# BTL__SCHESchDoc.net
KiCad netlist of a schematic drawn in Altium Designer
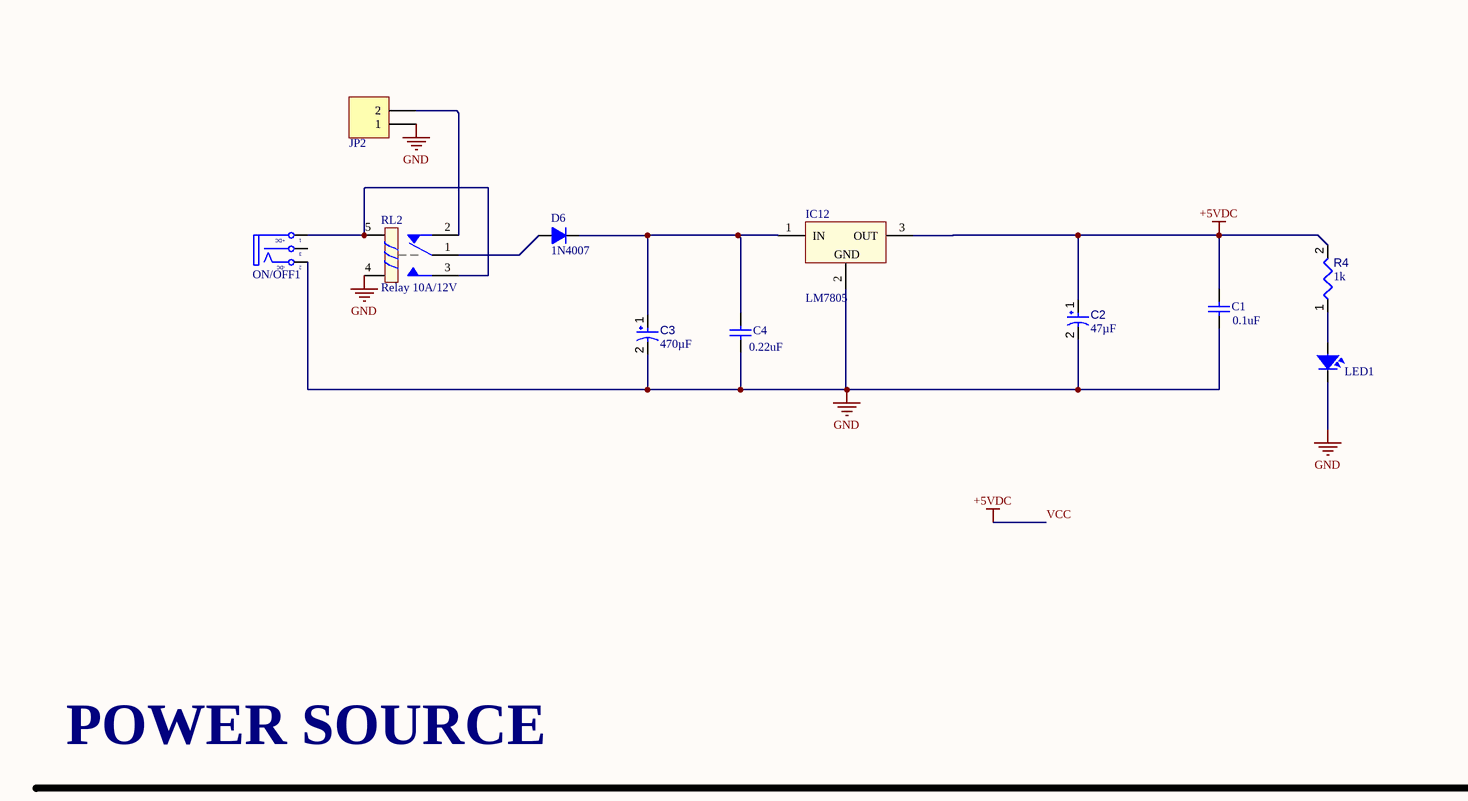
[diagram p0: BTL._SCHESchDoc.SchDoc, top left]
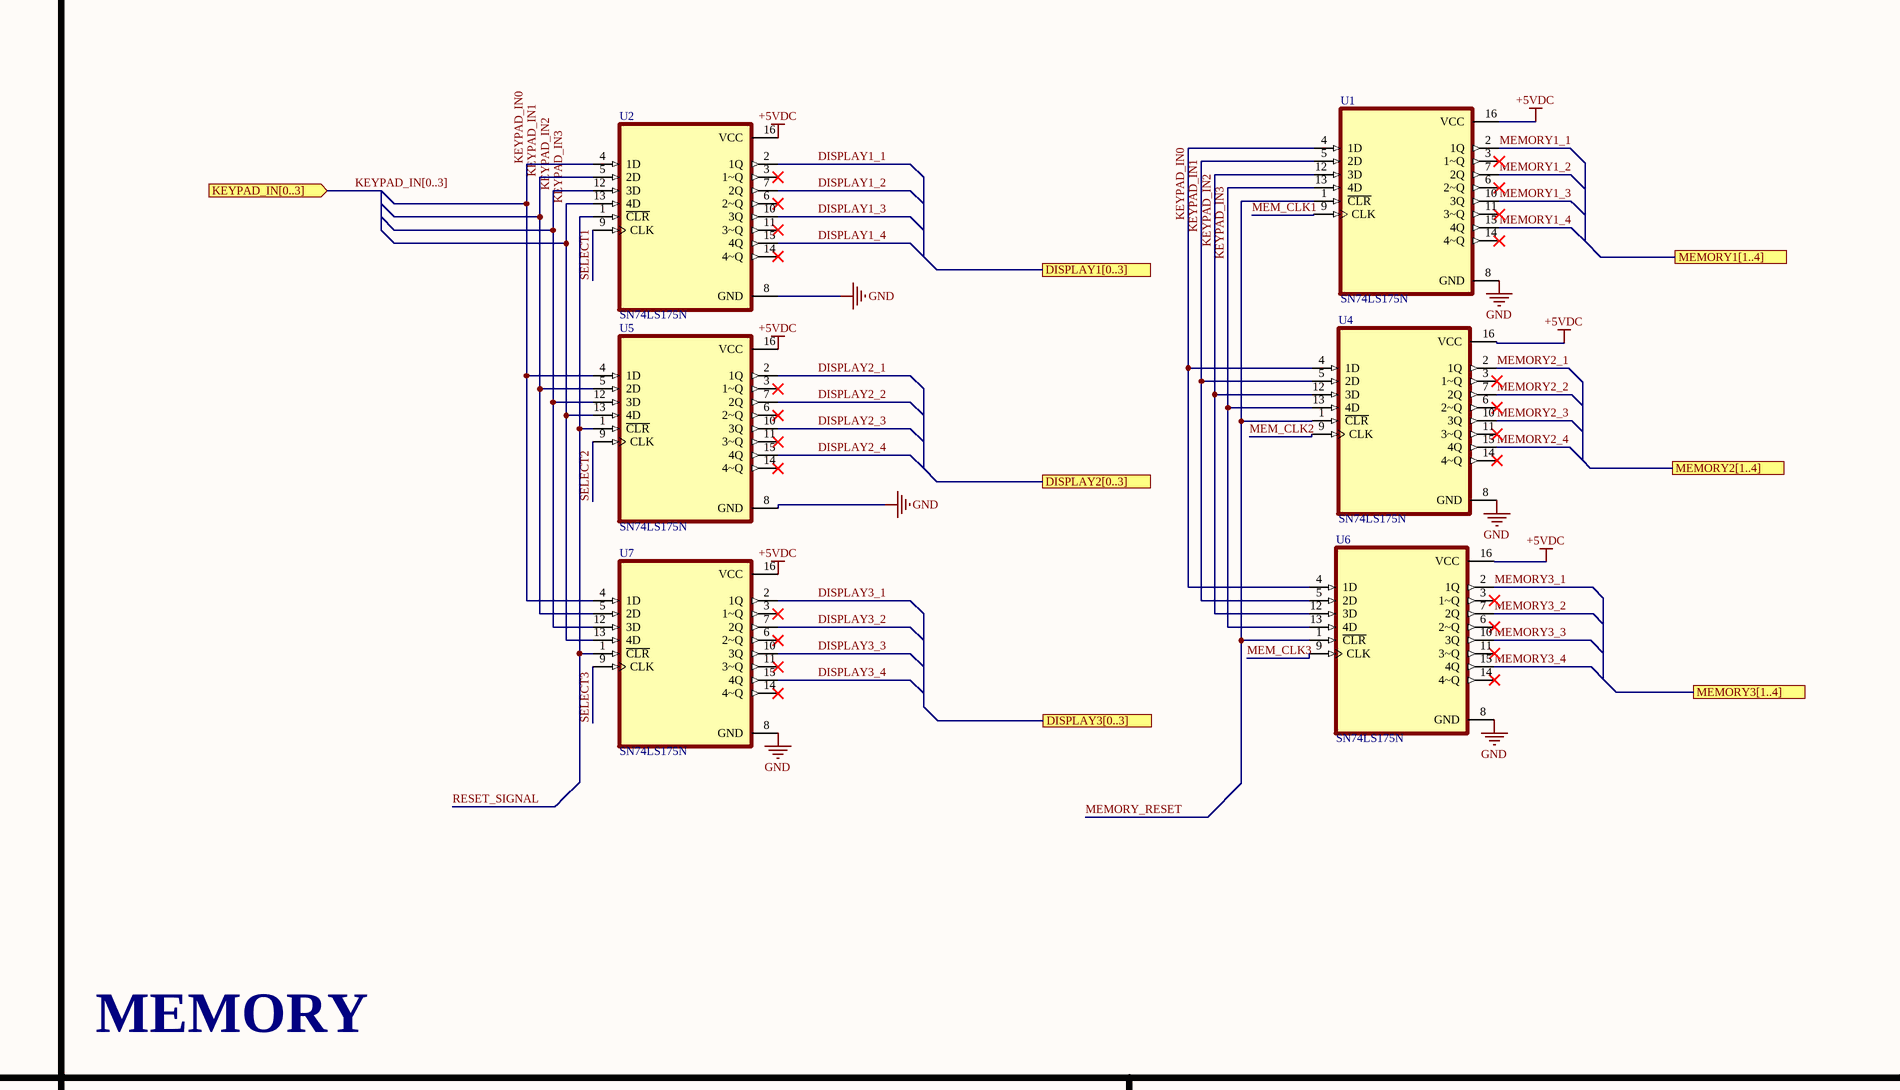
[diagram p1: BTL._SCHESchDoc.SchDoc, top middle]
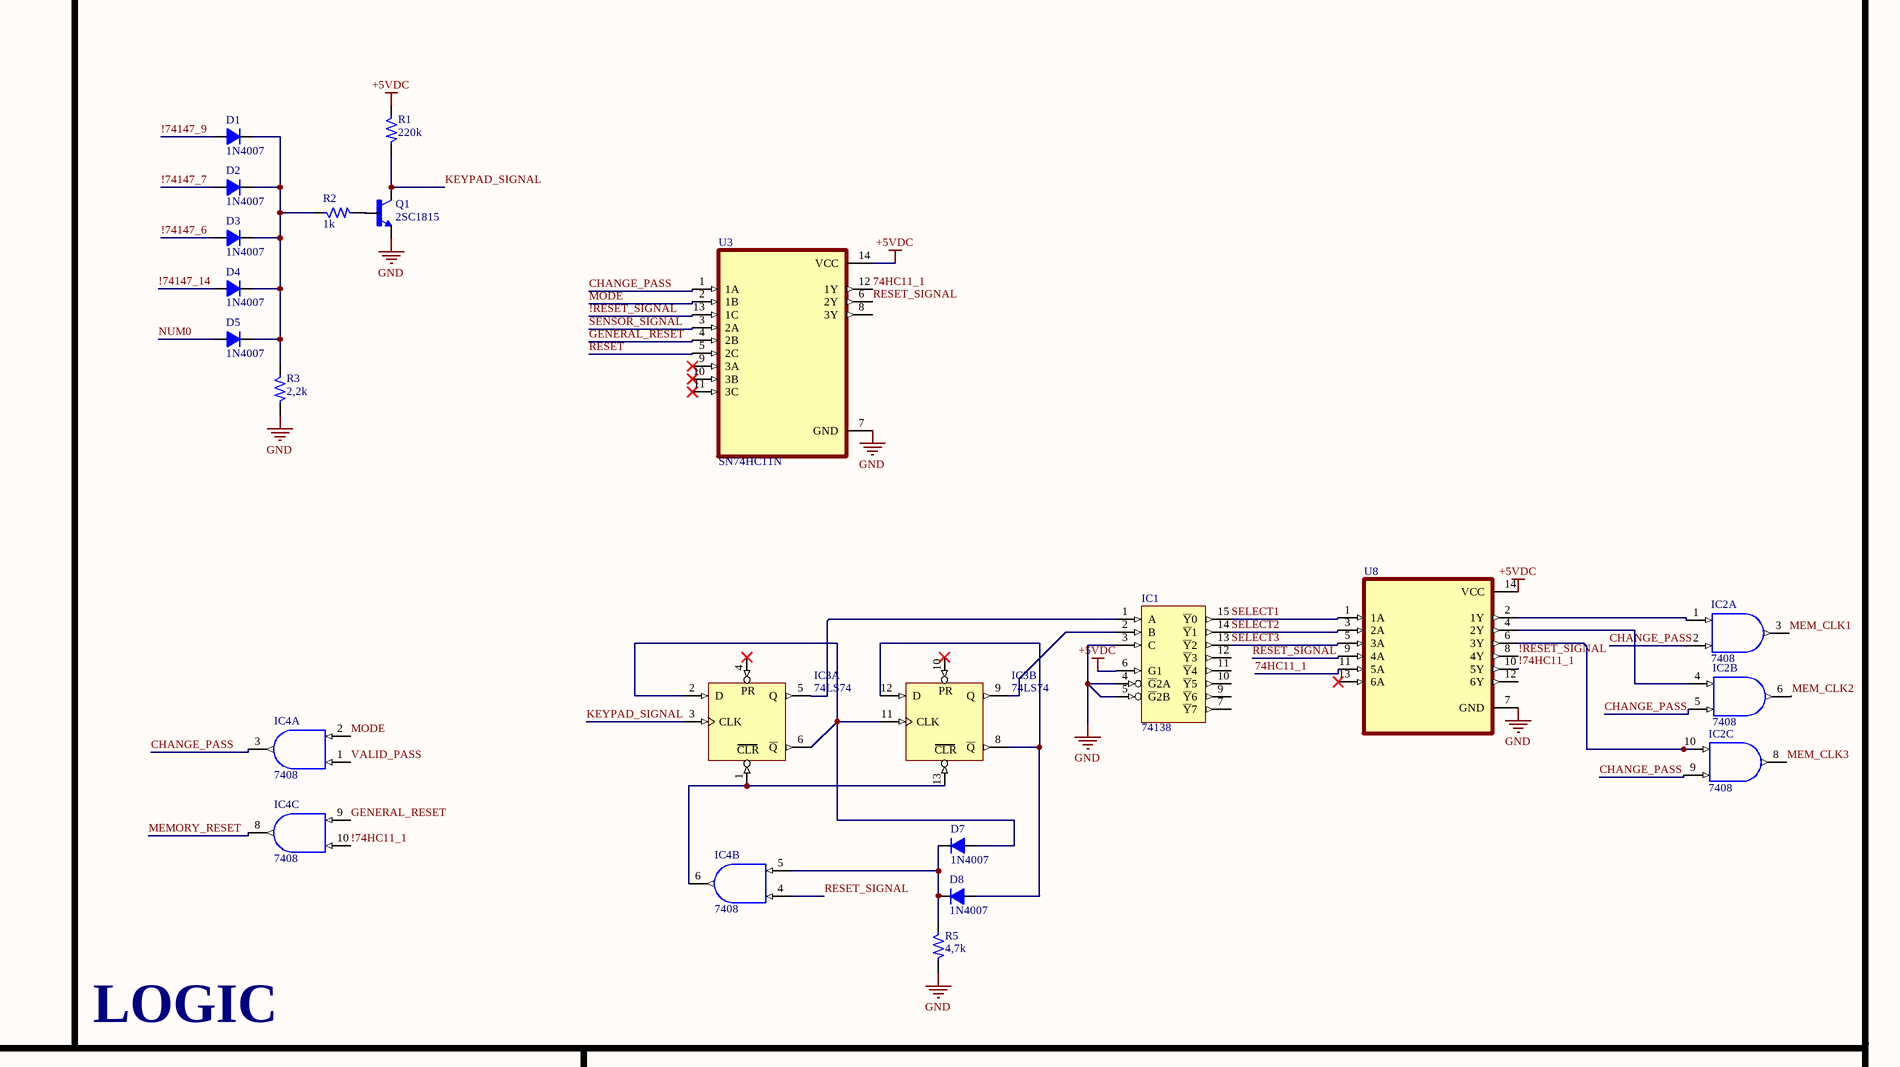
[diagram p2: BTL._SCHESchDoc.SchDoc, top right]
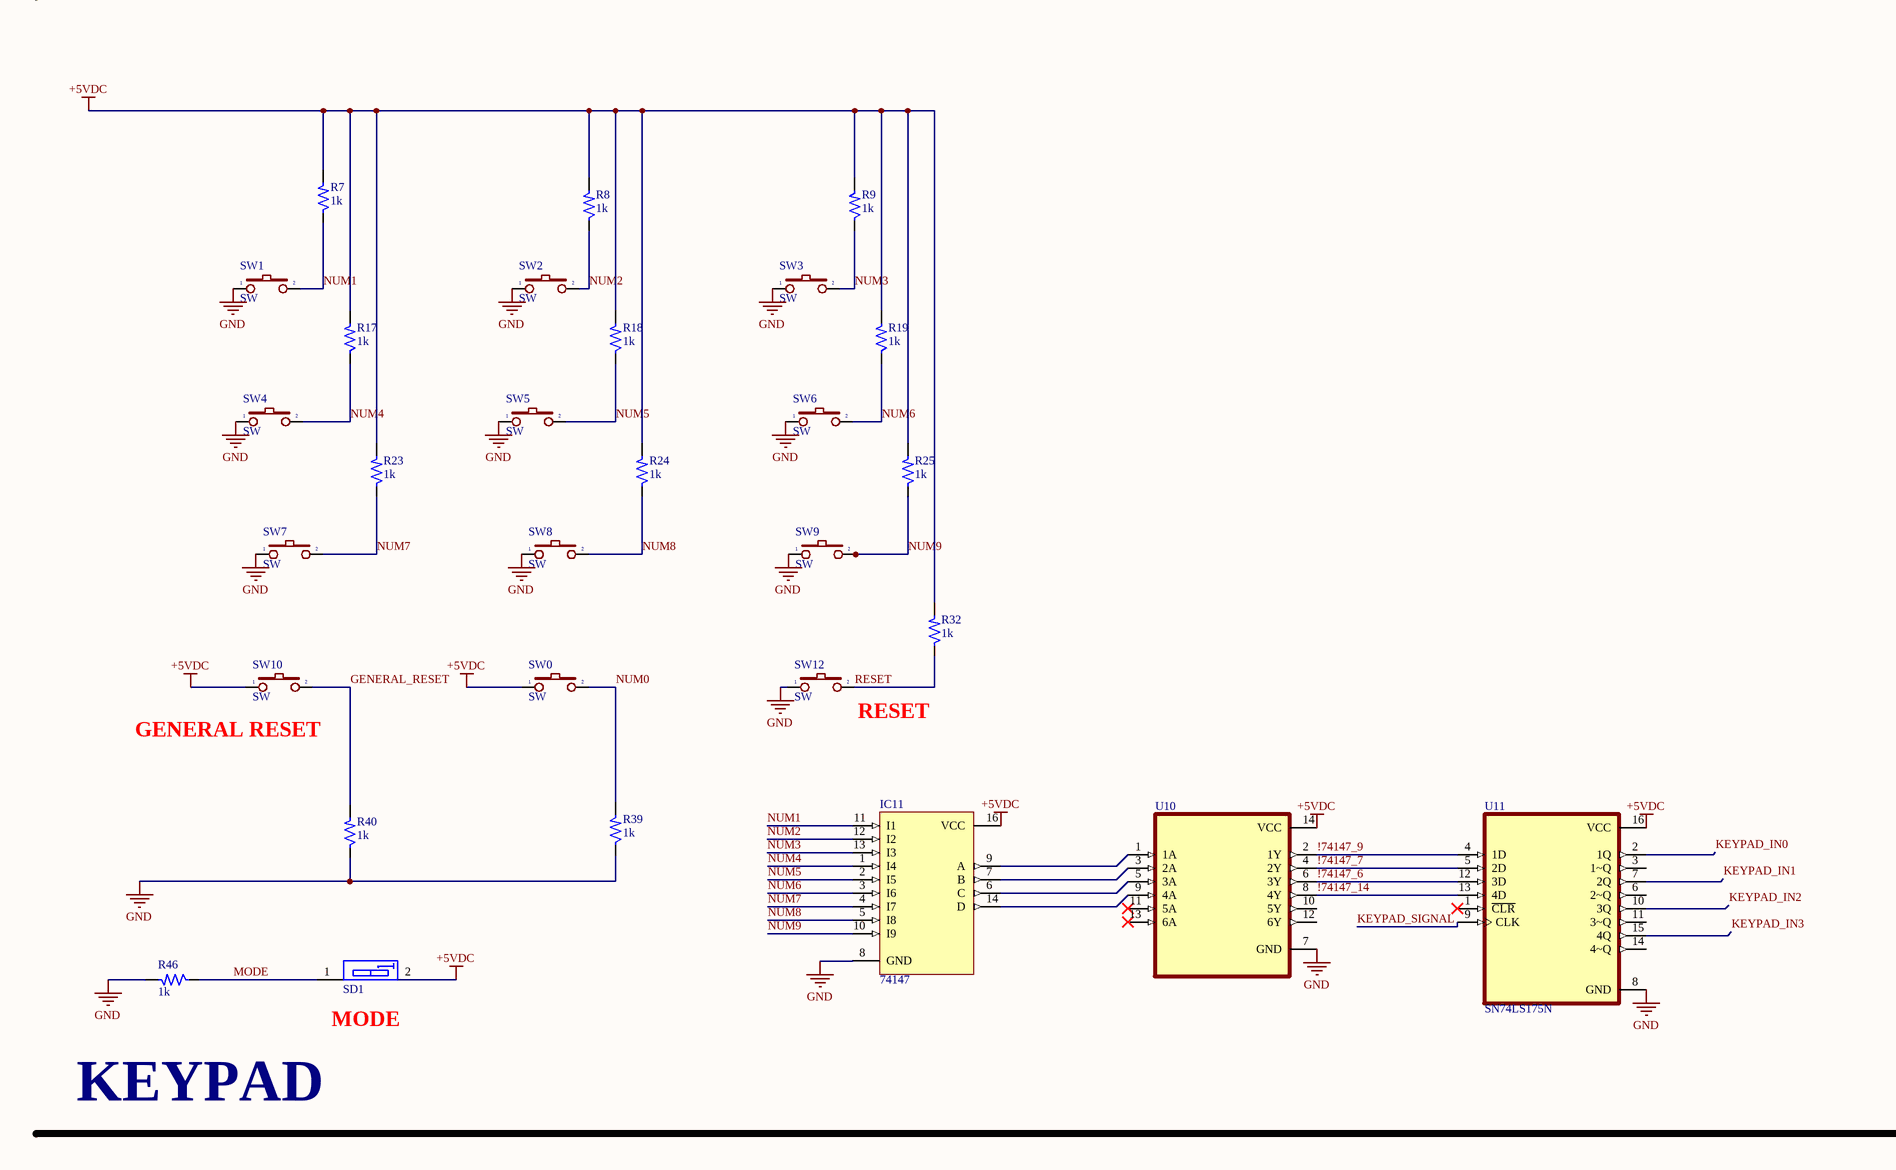
[diagram p3: BTL._SCHESchDoc.SchDoc, bottom left]
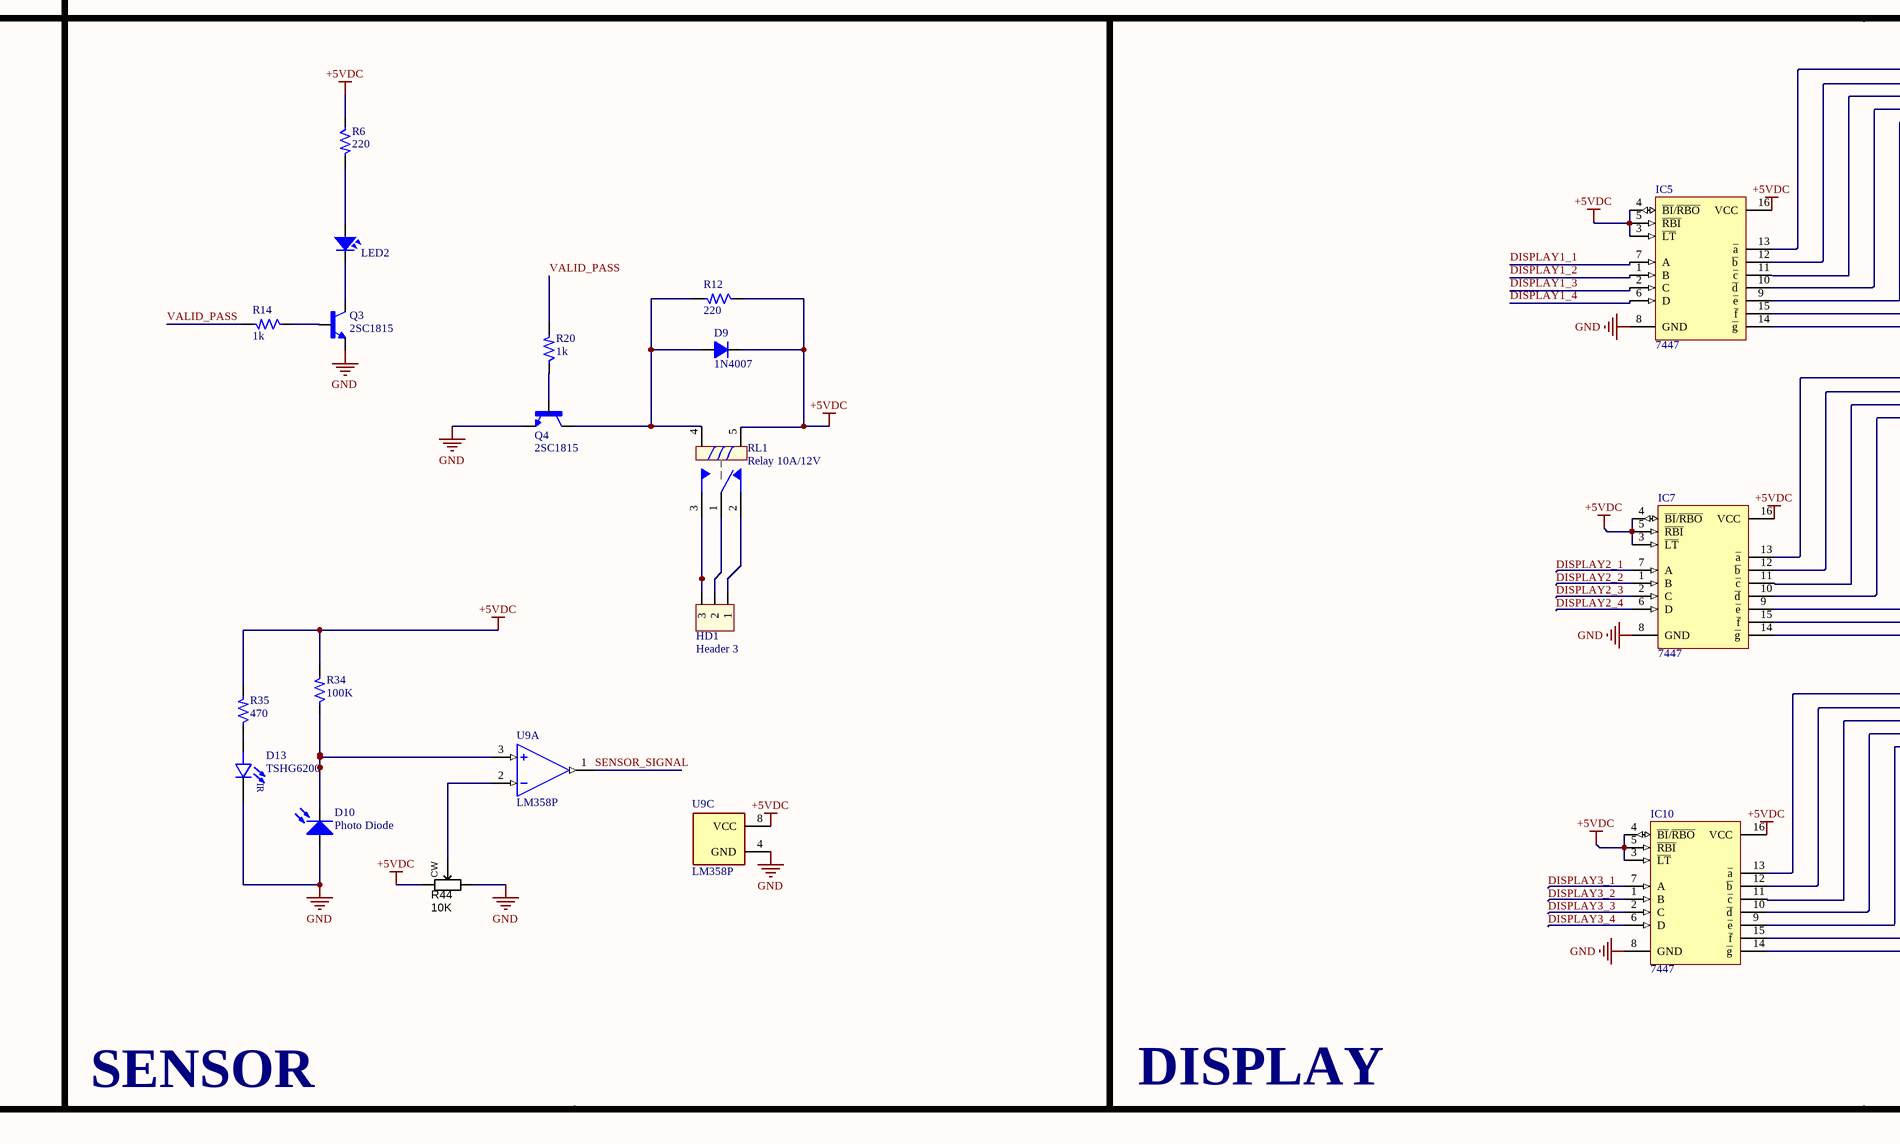
[diagram p4: BTL._SCHESchDoc.SchDoc, bottom middle]
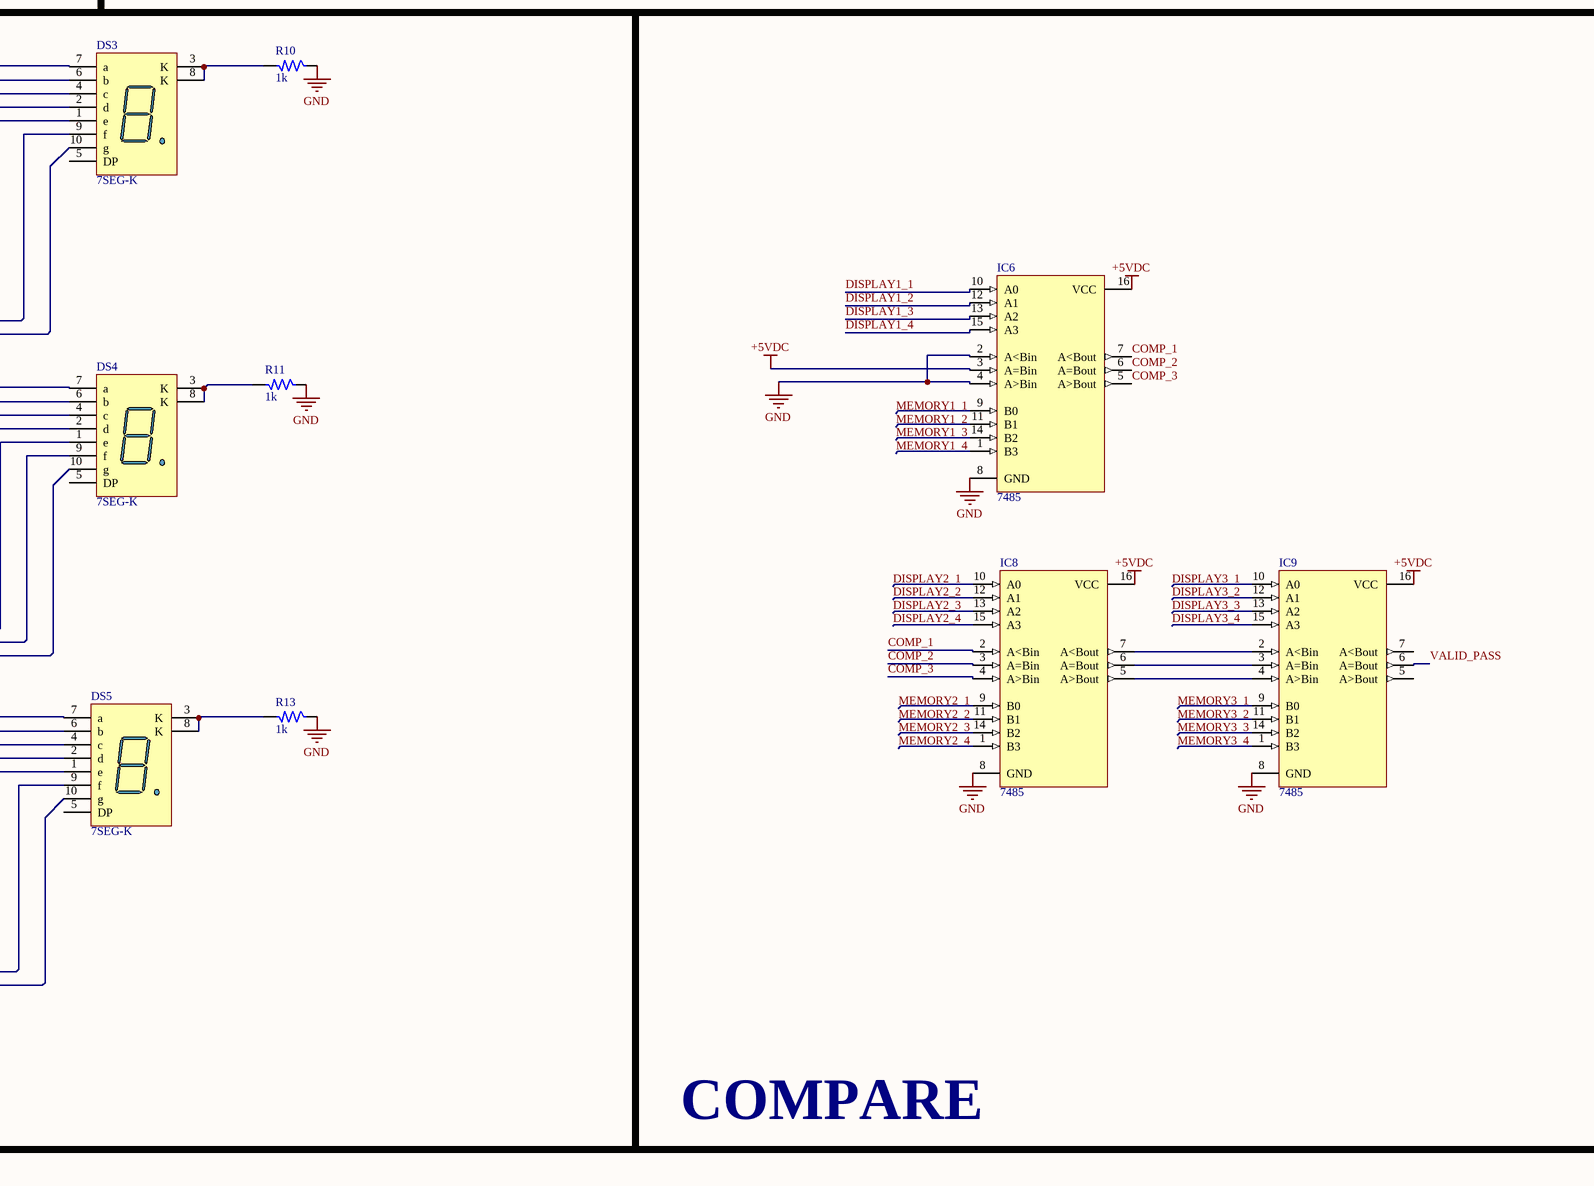
[diagram p5: BTL._SCHESchDoc.SchDoc, bottom right]

(export (version "E")
  (design (tool "Eeschema 10.0.6"))
  (components
    (comp (ref "C1")
      (value "Capacitor Ceramic 2KV")
      (footprint "103/2KV")
      (fields (field (name "PUBLISHER") "Altium Limited"))
      (libsource (lib "My library altium") (part "Cap 2KV"))
    )
    (comp (ref "C2")
      (value "47µF")
      (footprint "CAPPR55-250-1120X630X1220")
      (description "Aluminum Electrolytic Capacitor, 47 uF, +/-20%, 50 V, -40 to 85 degC, 2-Pin THD, RoHS, Bulk")
      (fields (field (name "TOLERANCE") "20%") (field (name "MANUFACTURER") "Panasonic"))
      (libsource (lib "Nam Nguyentbcm2711") (part "CAP-P-2"))
    )
    (comp (ref "C3")
      (value "470µF")
      (footprint "CAPPR65-500-2000X1000X2200")
      (description "Aluminum Electrolytic Capacitor, 470 uF, +/- 20%, 50 V, -40 to 85 degC, 2-Pin THD, RoHS, Bulk")
      (fields (field (name "TOLERANCE") "20%") (field (name "MANUFACTURER") "Panasonic"))
      (libsource (lib "Nam Nguyentbcm2711") (part "CAP-P-2"))
    )
    (comp (ref "C4")
      (value "Capacitor Ceramic 2KV")
      (footprint "103/2KV")
      (fields (field (name "PUBLISHER") "Altium Limited"))
      (libsource (lib "My library altium") (part "Cap 2KV"))
    )
    (comp (ref "D1")
      (value "1N4007")
      (footprint "D1A")
      (description "Diode 1A")
      (libsource (lib "syhaunguyen") (part "D1A"))
    )
    (comp (ref "D2")
      (value "1N4007")
      (footprint "D1A")
      (description "Diode 1A")
      (libsource (lib "syhaunguyen") (part "D1A"))
    )
    (comp (ref "D3")
      (value "1N4007")
      (footprint "D1A")
      (description "Diode 1A")
      (libsource (lib "syhaunguyen") (part "D1A"))
    )
    (comp (ref "D4")
      (value "1N4007")
      (footprint "D1A")
      (description "Diode 1A")
      (libsource (lib "syhaunguyen") (part "D1A"))
    )
    (comp (ref "D5")
      (value "1N4007")
      (footprint "D1A")
      (description "Diode 1A")
      (libsource (lib "syhaunguyen") (part "D1A"))
    )
    (comp (ref "D6")
      (value "1N4007")
      (footprint "D1A")
      (description "Diode 1A")
      (libsource (lib "syhaunguyen") (part "D1A"))
    )
    (comp (ref "D7")
      (value "1N4007")
      (footprint "D1A")
      (description "Diode 1A")
      (libsource (lib "syhaunguyen") (part "D1A"))
    )
    (comp (ref "D8")
      (value "1N4007")
      (footprint "D1A")
      (description "Diode 1A")
      (libsource (lib "syhaunguyen") (part "D1A"))
    )
    (comp (ref "D9")
      (value "1N4007")
      (footprint "D1A")
      (description "Diode 1A")
      (libsource (lib "syhaunguyen") (part "D1A"))
    )
    (comp (ref "D10")
      (value "Photo Diode")
      (footprint "LED-5")
      (description "Photosensitive Diode")
      (libsource (lib "My library altium") (part "Photo Diode"))
    )
    (comp (ref "D13")
      (value "TSHG6200")
      (footprint "LEDRD254W55D595H900")
      (description "850 nm 100 mA Â±10Â° Through Hole High Speed Infrared Emitting Diode - T-1 3/4 CT")
      (fields (field (name "MF") "{'manufacturer': u'Vishay'}"))
      (libsource (lib "SnapEDA_Library") (part "TSHG6200"))
    )
    (comp (ref "DS3")
      (value "7SEG-K")
      (footprint "LED7SEG")
      (description "14.2 mm General Purpose Blue 7-Segment Display: CC, RH DP, Gray Surface")
      (fields (field (name "PUBLISHER") "Altium Limited"))
      (libsource (lib "My library altium") (part "LED 7SEG-K"))
    )
    (comp (ref "DS4")
      (value "7SEG-K")
      (footprint "LED7SEG")
      (description "14.2 mm General Purpose Blue 7-Segment Display: CC, RH DP, Gray Surface")
      (fields (field (name "PUBLISHER") "Altium Limited"))
      (libsource (lib "My library altium") (part "LED 7SEG-K"))
    )
    (comp (ref "DS5")
      (value "7SEG-K")
      (footprint "LED7SEG")
      (description "14.2 mm General Purpose Blue 7-Segment Display: CC, RH DP, Gray Surface")
      (fields (field (name "PUBLISHER") "Altium Limited"))
      (libsource (lib "My library altium") (part "LED 7SEG-K"))
    )
    (comp (ref "HD1")
      (value "Header 3")
      (footprint "HED3")
      (description "Header 3 (Green)")
      (libsource (lib "syhaunguyen") (part "Hed3"))
    )
    (comp (ref "IC1")
      (value "74138")
      (footprint "DIP16/W0.3")
      (description "3 -to- 8 Decoder - Out Low")
      (fields (field (name "COPYRIGHT BY") "VanDungEvn@Gmail.com"))
      (libsource (lib "syhaunguyen") (part "74138"))
    )
    (comp (ref "IC2")
      (value "7408")
      (footprint "DIP14/W0.3")
      (description "Quad 2-Input AND Gate")
      (libsource (lib "My library altium") (part "7408"))
    )
    (comp (ref "IC3")
      (value "74LS74")
      (footprint "DIP14/W0.3")
      (description "Dual D Flip-Flop")
      (fields (field (name "COPYRIGHT BY") "VanDungEvn@Gmail.com"))
      (libsource (lib "syhaunguyen") (part "7474"))
    )
    (comp (ref "IC4")
      (value "7408")
      (footprint "DIP14/W0.3")
      (description "Quad 2-Input AND Gate")
      (libsource (lib "syhaunguyen") (part "7408"))
    )
    (comp (ref "IC5")
      (value "7447")
      (footprint "DIP16/W0.3")
      (description "BCD to 7-Segment Decoder/Driver")
      (libsource (lib "My library altium") (part "7447"))
    )
    (comp (ref "IC6")
      (value "7485")
      (footprint "DIP16/W0.3")
      (description "4-Bit Magnitude Comparator")
      (fields (field (name "COPYRIGHT BY") "VanDungEvn@Gmail.com"))
      (libsource (lib "My library altium") (part "7485"))
    )
    (comp (ref "IC7")
      (value "7447")
      (footprint "DIP16/W0.3")
      (description "BCD to 7-Segment Decoder/Driver")
      (libsource (lib "My library altium") (part "7447"))
    )
    (comp (ref "IC8")
      (value "7485")
      (footprint "DIP16/W0.3")
      (description "4-Bit Magnitude Comparator")
      (fields (field (name "COPYRIGHT BY") "VanDungEvn@Gmail.com"))
      (libsource (lib "My library altium") (part "7485"))
    )
    (comp (ref "IC9")
      (value "7485")
      (footprint "DIP16/W0.3")
      (description "4-Bit Magnitude Comparator")
      (fields (field (name "COPYRIGHT BY") "VanDungEvn@Gmail.com"))
      (libsource (lib "My library altium") (part "7485"))
    )
    (comp (ref "IC10")
      (value "7447")
      (footprint "DIP16/W0.3")
      (description "BCD to 7-Segment Decoder/Driver")
      (libsource (lib "My library altium") (part "7447"))
    )
    (comp (ref "IC11")
      (value "74147")
      (footprint "DIP16/W0.3")
      (description "10-Line to 4-Line Priority Encoder")
      (fields (field (name "COPYRIGHT BY") "VanDungEvn@Gmail.com"))
      (libsource (lib "My library altium") (part "74147"))
    )
    (comp (ref "IC12")
      (value "LM7805")
      (footprint "QTO-220")
      (description "On ap +, from + 5 to + 24VDC")
      (libsource (lib "My library altium") (part "LM78xx"))
    )
    (comp (ref "JP2")
      (value "Header 2_1")
      (footprint "HED2")
      (description "Header, 2-Pin")
      (fields (field (name "MANUFACTURER") "Generic Components"))
      (libsource (lib "syhaunguyen") (part "Header 2_1"))
    )
    (comp (ref "LED1")
      (value "LED")
      (footprint "LED-5-Green")
      (description "LED Single colour Green and Red")
      (libsource (lib "syhaunguyen") (part "LED"))
    )
    (comp (ref "LED2")
      (value "LED")
      (footprint "LED-5-Green")
      (description "LED Single colour Green and Red")
      (libsource (lib "syhaunguyen") (part "LED"))
    )
    (comp (ref "ON/OFF1")
      (value "POWER")
      (footprint "DC-IN")
      (libsource (lib "My library altium") (part "DCIN"))
    )
    (comp (ref "Q1")
      (value "2SC1815")
      (footprint "TO92127P521H534-3")
      (fields (field (name "MF") "{'manufacturer': u'Micro Commercial'}"))
      (libsource (lib "") (part "2SC1815_1"))
    )
    (comp (ref "Q3")
      (value "2SC1815")
      (footprint "TO92127P521H534-3")
      (fields (field (name "MF") "{'manufacturer': u'Micro Commercial'}"))
      (libsource (lib "") (part "2SC1815_1"))
    )
    (comp (ref "Q4")
      (value "2SC1815")
      (footprint "TO92127P521H534-3")
      (fields (field (name "MF") "{'manufacturer': u'Micro Commercial'}"))
      (libsource (lib "SnapEDA_Library") (part "2SC1815"))
    )
    (comp (ref "R1")
      (value "220k")
      (footprint "R1/4W3")
      (description "Res")
      (libsource (lib "My library altium") (part "Res"))
    )
    (comp (ref "R2")
      (value "1k")
      (footprint "R1/4W3")
      (description "Res")
      (libsource (lib "My library altium") (part "Res"))
    )
    (comp (ref "R3")
      (value "2,2k")
      (footprint "R1/4W3")
      (description "Res")
      (libsource (lib "My library altium") (part "Res"))
    )
    (comp (ref "R4")
      (value "1k")
      (footprint "RESA60-630X240")
      (description "Axial Resistor, 1 KOhm, +/- 1%, 250 mW, -55 to 155 degC, 2-Pin THD, RoHS, Bulk")
      (fields (field (name "TOLERANCE") "1%") (field (name "POWER") "250mW"))
      (libsource (lib "Nam Nguyentbcm2711") (part "RES-2"))
    )
    (comp (ref "R5")
      (value "4,7k")
      (footprint "R1/4W3")
      (description "Res")
      (libsource (lib "My library altium") (part "Res"))
    )
    (comp (ref "R6")
      (value "220")
      (footprint "R1/4W3")
      (description "Res")
      (libsource (lib "My library altium") (part "Res"))
    )
    (comp (ref "R7")
      (value "1k")
      (footprint "R1/4W3")
      (description "Res")
      (libsource (lib "My library altium") (part "Res"))
    )
    (comp (ref "R8")
      (value "1k")
      (footprint "R1/4W3")
      (description "Res")
      (libsource (lib "My library altium") (part "Res"))
    )
    (comp (ref "R9")
      (value "1k")
      (footprint "R1/4W3")
      (description "Res")
      (libsource (lib "My library altium") (part "Res"))
    )
    (comp (ref "R10")
      (value "1k")
      (footprint "R1/4W3")
      (description "Res")
      (libsource (lib "My library altium") (part "Res"))
    )
    (comp (ref "R11")
      (value "1k")
      (footprint "R1/4W3")
      (description "Res")
      (libsource (lib "My library altium") (part "Res"))
    )
    (comp (ref "R12")
      (value "220")
      (footprint "R1/4W3")
      (description "Res")
      (libsource (lib "My library altium") (part "Res"))
    )
    (comp (ref "R13")
      (value "1k")
      (footprint "R1/4W3")
      (description "Res")
      (libsource (lib "My library altium") (part "Res"))
    )
    (comp (ref "R14")
      (value "1k")
      (footprint "R1/4W3")
      (description "Res")
      (libsource (lib "My library altium") (part "Res"))
    )
    (comp (ref "R17")
      (value "1k")
      (footprint "R1/4W3")
      (description "Res")
      (libsource (lib "My library altium") (part "Res"))
    )
    (comp (ref "R18")
      (value "1k")
      (footprint "R1/4W3")
      (description "Res")
      (libsource (lib "My library altium") (part "Res"))
    )
    (comp (ref "R19")
      (value "1k")
      (footprint "R1/4W3")
      (description "Res")
      (libsource (lib "My library altium") (part "Res"))
    )
    (comp (ref "R20")
      (value "1k")
      (footprint "R1/4W3")
      (description "Res")
      (libsource (lib "My library altium") (part "Res"))
    )
    (comp (ref "R23")
      (value "1k")
      (footprint "R1/4W3")
      (description "Res")
      (libsource (lib "My library altium") (part "Res"))
    )
    (comp (ref "R24")
      (value "1k")
      (footprint "R1/4W3")
      (description "Res")
      (libsource (lib "My library altium") (part "Res"))
    )
    (comp (ref "R25")
      (value "1k")
      (footprint "R1/4W3")
      (description "Res")
      (libsource (lib "My library altium") (part "Res"))
    )
    (comp (ref "R32")
      (value "1k")
      (footprint "R1/4W3")
      (description "Res")
      (libsource (lib "My library altium") (part "Res"))
    )
    (comp (ref "R34")
      (value "100K")
      (footprint "R1/4W3")
      (description "Res")
      (libsource (lib "My library altium") (part "Res"))
    )
    (comp (ref "R35")
      (value "470")
      (footprint "R1/4W3")
      (description "Res")
      (libsource (lib "My library altium") (part "Res"))
    )
    (comp (ref "R39")
      (value "1k")
      (footprint "R1/4W3")
      (description "Res")
      (libsource (lib "My library altium") (part "Res"))
    )
    (comp (ref "R40")
      (value "1k")
      (footprint "R1/4W3")
      (description "Res")
      (libsource (lib "My library altium") (part "Res"))
    )
    (comp (ref "R44")
      (value "10K")
      (footprint "POT_3306F")
      (description "Trimmer THD 10K 200mW Single-turn")
      (fields (field (name "TOLERANCE") "±25%") (field (name "Comment") "Single-turn pot"))
      (libsource (lib "My library altium") (part "RES_TRIMMER_10K_1T_THT"))
    )
    (comp (ref "R46")
      (value "1k")
      (footprint "R1/4W3")
      (description "Res")
      (libsource (lib "My library altium") (part "Res"))
    )
    (comp (ref "RL1")
      (value "Relay 10A/12V")
      (footprint "RL_SPDT_10A")
      (description "Relay SPDT,10A - 12VDC 5 Pin")
      (libsource (lib "") (part "Relay 1_1"))
    )
    (comp (ref "RL2")
      (value "Relay 10A/12V")
      (footprint "RL_SPDT_10A")
      (description "Relay SPDT,10A - 12VDC 5 Pin")
      (libsource (lib "syhaunguyen") (part "Relay 1"))
    )
    (comp (ref "SD1")
      (value "SW - DIP2")
      (footprint "DIP2/W0.3K")
      (description "DIP Switch, 2 Position, SPST")
      (libsource (lib "My library altium") (part "SWDIP-1"))
    )
    (comp (ref "SW0")
      (value "SW")
      (footprint "SW2")
      (description "Switch button 2 pin")
      (libsource (lib "syhaunguyen") (part "SW2"))
    )
    (comp (ref "SW1")
      (value "SW")
      (footprint "SW2")
      (description "Switch button 2 pin")
      (libsource (lib "syhaunguyen") (part "SW2"))
    )
    (comp (ref "SW2")
      (value "SW")
      (footprint "SW2")
      (description "Switch button 2 pin")
      (libsource (lib "syhaunguyen") (part "SW2"))
    )
    (comp (ref "SW3")
      (value "SW")
      (footprint "SW2")
      (description "Switch button 2 pin")
      (libsource (lib "syhaunguyen") (part "SW2"))
    )
    (comp (ref "SW4")
      (value "SW")
      (footprint "SW2")
      (description "Switch button 2 pin")
      (libsource (lib "syhaunguyen") (part "SW2"))
    )
    (comp (ref "SW5")
      (value "SW")
      (footprint "SW2")
      (description "Switch button 2 pin")
      (libsource (lib "syhaunguyen") (part "SW2"))
    )
    (comp (ref "SW6")
      (value "SW")
      (footprint "SW2")
      (description "Switch button 2 pin")
      (libsource (lib "syhaunguyen") (part "SW2"))
    )
    (comp (ref "SW7")
      (value "SW")
      (footprint "SW2")
      (description "Switch button 2 pin")
      (libsource (lib "syhaunguyen") (part "SW2"))
    )
    (comp (ref "SW8")
      (value "SW")
      (footprint "SW2")
      (description "Switch button 2 pin")
      (libsource (lib "syhaunguyen") (part "SW2"))
    )
    (comp (ref "SW9")
      (value "SW")
      (footprint "SW2")
      (description "Switch button 2 pin")
      (libsource (lib "syhaunguyen") (part "SW2"))
    )
    (comp (ref "SW10")
      (value "SW")
      (footprint "SW2")
      (description "Switch button 2 pin")
      (libsource (lib "syhaunguyen") (part "SW2"))
    )
    (comp (ref "SW12")
      (value "SW")
      (footprint "SW2")
      (description "Switch button 2 pin")
      (libsource (lib "syhaunguyen") (part "SW2"))
    )
    (comp (ref "U1")
      (value "SN74LS175N")
      (footprint "DIP16")
      (fields (field (name "MF") "{'manufacturer': u'Texas Instruments'}"))
      (libsource (lib "SnapEDA_Library") (part "SN74LS175N"))
    )
    (comp (ref "U2")
      (value "SN74LS175N")
      (footprint "DIP16")
      (fields (field (name "MF") "{'manufacturer': u'Texas Instruments'}"))
      (libsource (lib "SnapEDA_Library") (part "SN74LS175N"))
    )
    (comp (ref "U3")
      (value "SN74HC11N")
      (footprint "DIP14/W0.3")
      (libsource (lib "SN74HC11N") (part "SN74HC11N"))
    )
    (comp (ref "U4")
      (value "SN74LS175N")
      (footprint "DIP16")
      (fields (field (name "MF") "{'manufacturer': u'Texas Instruments'}"))
      (libsource (lib "SnapEDA_Library") (part "SN74LS175N"))
    )
    (comp (ref "U5")
      (value "SN74LS175N")
      (footprint "DIP16")
      (fields (field (name "MF") "{'manufacturer': u'Texas Instruments'}"))
      (libsource (lib "SnapEDA_Library") (part "SN74LS175N"))
    )
    (comp (ref "U6")
      (value "SN74LS175N")
      (footprint "DIP16")
      (fields (field (name "MF") "{'manufacturer': u'Texas Instruments'}"))
      (libsource (lib "SnapEDA_Library") (part "SN74LS175N"))
    )
    (comp (ref "U7")
      (value "SN74LS175N")
      (footprint "DIP16")
      (fields (field (name "MF") "{'manufacturer': u'Texas Instruments'}"))
      (libsource (lib "SnapEDA_Library") (part "SN74LS175N"))
    )
    (comp (ref "U8")
      (value "~")
      (footprint "DIP14/W0.3")
      (description "6-ch, 4.75-V to 5.25-V bipolar inverters")
      (fields (field (name "MF") "Texas Instruments") (field (name "MP") "SN74LS04N"))
      (libsource (lib "SN74LS04N") (part "SN74LS04N"))
    )
    (comp (ref "U9")
      (value "LM358P")
      (footprint "DIP8")
      (fields (field (name "MF") "{'manufacturer': u'Texas Instruments'}"))
      (libsource (lib "SnapEDA_Library") (part "LM358P"))
    )
    (comp (ref "U10")
      (value "~")
      (footprint "DIP14/W0.3")
      (description "6-ch, 4.75-V to 5.25-V bipolar inverters")
      (fields (field (name "MF") "Texas Instruments") (field (name "MP") "SN74LS04N"))
      (libsource (lib "SN74LS04N") (part "SN74LS04N"))
    )
    (comp (ref "U11")
      (value "SN74LS175N")
      (footprint "DIP16")
      (description "Quadruple D-Type Flip-Flops With Clear 16-PDIP 0 to 70")
      (fields (field (name "MF") "Texas Instruments") (field (name "DIGI-KEY_PART_NUMBER") "296-28719-2-ND"))
      (libsource (lib "SN74LS175N") (part "SN74LS175N"))
    )
  )
  (nets
    (net (code "25") (name "+5VDC") (class "Default")
      (node (ref "C1") (pin "2") (pinfunction "2_2") (pintype "passive"))
      (node (ref "C2") (pin "1") (pinfunction "1_1") (pintype "passive"))
      (node (ref "D9") (pin "2") (pinfunction "K_2") (pintype "passive"))
      (node (ref "IC1") (pin "16") (pinfunction "VCC_16") (pintype "power_in"))
      (node (ref "IC1") (pin "6") (pinfunction "G1_6") (pintype "input"))
      (node (ref "IC10") (pin "16") (pinfunction "VCC_16") (pintype "power_in"))
      (node (ref "IC10") (pin "3") (pinfunction "~{LT}_3") (pintype "input"))
      (node (ref "IC10") (pin "4") (pinfunction "~{BI}/~{RBO}_4") (pintype "bidirectional"))
      (node (ref "IC10") (pin "5") (pinfunction "~{RBI}_5") (pintype "input"))
      (node (ref "IC11") (pin "16") (pinfunction "VCC_16") (pintype "power_in"))
      (node (ref "IC12") (pin "3") (pinfunction "OUT_3") (pintype "passive"))
      (node (ref "IC2") (pin "14") (pinfunction "VCC_14") (pintype "power_in"))
      (node (ref "IC3") (pin "14") (pinfunction "VCC_14") (pintype "power_in"))
      (node (ref "IC4") (pin "14") (pinfunction "VCC_14") (pintype "power_in"))
      (node (ref "IC5") (pin "16") (pinfunction "VCC_16") (pintype "power_in"))
      (node (ref "IC5") (pin "3") (pinfunction "~{LT}_3") (pintype "input"))
      (node (ref "IC5") (pin "4") (pinfunction "~{BI}/~{RBO}_4") (pintype "bidirectional"))
      (node (ref "IC5") (pin "5") (pinfunction "~{RBI}_5") (pintype "input"))
      (node (ref "IC6") (pin "16") (pinfunction "VCC_16") (pintype "power_in"))
      (node (ref "IC6") (pin "3") (pinfunction "A=Bin_3") (pintype "input"))
      (node (ref "IC7") (pin "16") (pinfunction "VCC_16") (pintype "power_in"))
      (node (ref "IC7") (pin "3") (pinfunction "~{LT}_3") (pintype "input"))
      (node (ref "IC7") (pin "4") (pinfunction "~{BI}/~{RBO}_4") (pintype "bidirectional"))
      (node (ref "IC7") (pin "5") (pinfunction "~{RBI}_5") (pintype "input"))
      (node (ref "IC8") (pin "16") (pinfunction "VCC_16") (pintype "power_in"))
      (node (ref "IC9") (pin "16") (pinfunction "VCC_16") (pintype "power_in"))
      (node (ref "R1") (pin "1") (pinfunction "1_1") (pintype "passive"))
      (node (ref "R12") (pin "1") (pinfunction "1_1") (pintype "passive"))
      (node (ref "R17") (pin "2") (pinfunction "2_2") (pintype "passive"))
      (node (ref "R18") (pin "2") (pinfunction "2_2") (pintype "passive"))
      (node (ref "R19") (pin "2") (pinfunction "2_2") (pintype "passive"))
      (node (ref "R23") (pin "2") (pinfunction "2_2") (pintype "passive"))
      (node (ref "R24") (pin "2") (pinfunction "2_2") (pintype "passive"))
      (node (ref "R25") (pin "2") (pinfunction "2_2") (pintype "passive"))
      (node (ref "R32") (pin "2") (pinfunction "2_2") (pintype "passive"))
      (node (ref "R34") (pin "2") (pinfunction "2_2") (pintype "passive"))
      (node (ref "R35") (pin "2") (pinfunction "2_2") (pintype "passive"))
      (node (ref "R4") (pin "2") (pinfunction "2_2") (pintype "passive"))
      (node (ref "R44") (pin "CW") (pinfunction "3_CW") (pintype "passive"))
      (node (ref "R6") (pin "1") (pinfunction "1_1") (pintype "passive"))
      (node (ref "R7") (pin "2") (pinfunction "2_2") (pintype "passive"))
      (node (ref "R8") (pin "2") (pinfunction "2_2") (pintype "passive"))
      (node (ref "R9") (pin "2") (pinfunction "2_2") (pintype "passive"))
      (node (ref "RL1") (pin "5") (pinfunction "5_5") (pintype "passive"))
      (node (ref "SD1") (pin "2") (pinfunction "A2_2") (pintype "passive"))
      (node (ref "SW0") (pin "1") (pinfunction "1_1") (pintype "passive"))
      (node (ref "SW10") (pin "1") (pinfunction "1_1") (pintype "passive"))
      (node (ref "U1") (pin "16") (pinfunction "VCC_16") (pintype "power_in"))
      (node (ref "U10") (pin "14") (pinfunction "VCC_14") (pintype "power_in"))
      (node (ref "U11") (pin "16") (pinfunction "VCC_16") (pintype "power_in"))
      (node (ref "U2") (pin "16") (pinfunction "VCC_16") (pintype "power_in"))
      (node (ref "U3") (pin "14") (pinfunction "VCC_14") (pintype "power_in"))
      (node (ref "U4") (pin "16") (pinfunction "VCC_16") (pintype "power_in"))
      (node (ref "U5") (pin "16") (pinfunction "VCC_16") (pintype "power_in"))
      (node (ref "U6") (pin "16") (pinfunction "VCC_16") (pintype "power_in"))
      (node (ref "U7") (pin "16") (pinfunction "VCC_16") (pintype "power_in"))
      (node (ref "U8") (pin "14") (pinfunction "VCC_14") (pintype "power_in"))
      (node (ref "U9") (pin "8") (pinfunction "VCC_8") (pintype "power_in"))
    )
    (net (code "26") (name "/!74HC11_1") (class "Default")
      (node (ref "IC4") (pin "10") (pinfunction "A_10") (pintype "input"))
      (node (ref "U8") (pin "10") (pinfunction "5Y_10") (pintype "output"))
    )
    (net (code "27") (name "/!74147_6") (class "Default")
      (node (ref "D3") (pin "1") (pinfunction "A_1") (pintype "passive"))
      (node (ref "U10") (pin "6") (pinfunction "3Y_6") (pintype "output"))
      (node (ref "U11") (pin "12") (pinfunction "3D_12") (pintype "input"))
    )
    (net (code "28") (name "/!74147_7") (class "Default")
      (node (ref "D2") (pin "1") (pinfunction "A_1") (pintype "passive"))
      (node (ref "U10") (pin "4") (pinfunction "2Y_4") (pintype "output"))
      (node (ref "U11") (pin "5") (pinfunction "2D_5") (pintype "input"))
    )
    (net (code "29") (name "/!74147_9") (class "Default")
      (node (ref "D1") (pin "1") (pinfunction "A_1") (pintype "passive"))
      (node (ref "U10") (pin "2") (pinfunction "1Y_2") (pintype "output"))
      (node (ref "U11") (pin "4") (pinfunction "1D_4") (pintype "input"))
    )
    (net (code "30") (name "/!74147_14") (class "Default")
      (node (ref "D4") (pin "1") (pinfunction "A_1") (pintype "passive"))
      (node (ref "U10") (pin "8") (pinfunction "4Y_8") (pintype "output"))
      (node (ref "U11") (pin "13") (pinfunction "4D_13") (pintype "input"))
    )
    (net (code "31") (name "/!RESET_SIGNAL") (class "Default")
      (node (ref "U3") (pin "13") (pinfunction "1C_13") (pintype "input"))
      (node (ref "U8") (pin "8") (pinfunction "4Y_8") (pintype "output"))
    )
    (net (code "32") (name "/74HC11_1") (class "Default")
      (node (ref "U3") (pin "12") (pinfunction "1Y_12") (pintype "output"))
      (node (ref "U8") (pin "11") (pinfunction "5A_11") (pintype "input"))
    )
    (net (code "33") (name "/CHANGE_PASS") (class "Default")
      (node (ref "IC2") (pin "2") (pinfunction "B_2") (pintype "input"))
      (node (ref "IC2") (pin "5") (pinfunction "B_5") (pintype "input"))
      (node (ref "IC2") (pin "9") (pinfunction "B_9") (pintype "input"))
      (node (ref "IC4") (pin "3") (pinfunction "O_3") (pintype "output"))
      (node (ref "U3") (pin "1") (pinfunction "1A_1") (pintype "input"))
    )
    (net (code "34") (name "/COMP_1") (class "Default")
      (node (ref "IC6") (pin "7") (pinfunction "A<Bout_7") (pintype "output"))
      (node (ref "IC8") (pin "2") (pinfunction "A<Bin_2") (pintype "input"))
    )
    (net (code "35") (name "/COMP_2") (class "Default")
      (node (ref "IC6") (pin "6") (pinfunction "A=Bout_6") (pintype "output"))
      (node (ref "IC8") (pin "3") (pinfunction "A=Bin_3") (pintype "input"))
    )
    (net (code "36") (name "/COMP_3") (class "Default")
      (node (ref "IC6") (pin "5") (pinfunction "A>Bout_5") (pintype "output"))
      (node (ref "IC8") (pin "4") (pinfunction "A>Bin_4") (pintype "input"))
    )
    (net (code "38") (name "/DISPLAY1_1") (class "Default")
      (node (ref "IC5") (pin "7") (pinfunction "A_7") (pintype "input"))
      (node (ref "IC6") (pin "10") (pinfunction "A0_10") (pintype "input"))
      (node (ref "U2") (pin "2") (pinfunction "1Q_2") (pintype "output"))
    )
    (net (code "39") (name "/DISPLAY1_2") (class "Default")
      (node (ref "IC5") (pin "1") (pinfunction "B_1") (pintype "input"))
      (node (ref "IC6") (pin "12") (pinfunction "A1_12") (pintype "input"))
      (node (ref "U2") (pin "7") (pinfunction "2Q_7") (pintype "output"))
    )
    (net (code "40") (name "/DISPLAY1_3") (class "Default")
      (node (ref "IC5") (pin "2") (pinfunction "C_2") (pintype "input"))
      (node (ref "IC6") (pin "13") (pinfunction "A2_13") (pintype "input"))
      (node (ref "U2") (pin "10") (pinfunction "3Q_10") (pintype "output"))
    )
    (net (code "41") (name "/DISPLAY1_4") (class "Default")
      (node (ref "IC5") (pin "6") (pinfunction "D_6") (pintype "input"))
      (node (ref "IC6") (pin "15") (pinfunction "A3_15") (pintype "input"))
      (node (ref "U2") (pin "15") (pinfunction "4Q_15") (pintype "output"))
    )
    (net (code "43") (name "/DISPLAY2_1") (class "Default")
      (node (ref "IC7") (pin "7") (pinfunction "A_7") (pintype "input"))
      (node (ref "IC8") (pin "10") (pinfunction "A0_10") (pintype "input"))
      (node (ref "U5") (pin "2") (pinfunction "1Q_2") (pintype "output"))
    )
    (net (code "44") (name "/DISPLAY2_2") (class "Default")
      (node (ref "IC7") (pin "1") (pinfunction "B_1") (pintype "input"))
      (node (ref "IC8") (pin "12") (pinfunction "A1_12") (pintype "input"))
      (node (ref "U5") (pin "7") (pinfunction "2Q_7") (pintype "output"))
    )
    (net (code "45") (name "/DISPLAY2_3") (class "Default")
      (node (ref "IC7") (pin "2") (pinfunction "C_2") (pintype "input"))
      (node (ref "IC8") (pin "13") (pinfunction "A2_13") (pintype "input"))
      (node (ref "U5") (pin "10") (pinfunction "3Q_10") (pintype "output"))
    )
    (net (code "46") (name "/DISPLAY2_4") (class "Default")
      (node (ref "IC7") (pin "6") (pinfunction "D_6") (pintype "input"))
      (node (ref "IC8") (pin "15") (pinfunction "A3_15") (pintype "input"))
      (node (ref "U5") (pin "15") (pinfunction "4Q_15") (pintype "output"))
    )
    (net (code "48") (name "/DISPLAY3_1") (class "Default")
      (node (ref "IC10") (pin "7") (pinfunction "A_7") (pintype "input"))
      (node (ref "IC9") (pin "10") (pinfunction "A0_10") (pintype "input"))
      (node (ref "U7") (pin "2") (pinfunction "1Q_2") (pintype "output"))
    )
    (net (code "49") (name "/DISPLAY3_2") (class "Default")
      (node (ref "IC10") (pin "1") (pinfunction "B_1") (pintype "input"))
      (node (ref "IC9") (pin "12") (pinfunction "A1_12") (pintype "input"))
      (node (ref "U7") (pin "7") (pinfunction "2Q_7") (pintype "output"))
    )
    (net (code "50") (name "/DISPLAY3_3") (class "Default")
      (node (ref "IC10") (pin "2") (pinfunction "C_2") (pintype "input"))
      (node (ref "IC9") (pin "13") (pinfunction "A2_13") (pintype "input"))
      (node (ref "U7") (pin "10") (pinfunction "3Q_10") (pintype "output"))
    )
    (net (code "51") (name "/DISPLAY3_4") (class "Default")
      (node (ref "IC10") (pin "6") (pinfunction "D_6") (pintype "input"))
      (node (ref "IC9") (pin "15") (pinfunction "A3_15") (pintype "input"))
      (node (ref "U7") (pin "15") (pinfunction "4Q_15") (pintype "output"))
    )
    (net (code "52") (name "/GENERAL_RESET") (class "Default")
      (node (ref "IC4") (pin "9") (pinfunction "B_9") (pintype "input"))
      (node (ref "R40") (pin "2") (pinfunction "2_2") (pintype "passive"))
      (node (ref "SW10") (pin "2") (pinfunction "2_2") (pintype "passive"))
      (node (ref "U3") (pin "4") (pinfunction "2B_4") (pintype "input"))
    )
    (net (code "53") (name "/KEYPAD_IN0") (class "Default")
      (node (ref "U1") (pin "4") (pinfunction "1D_4") (pintype "input"))
      (node (ref "U11") (pin "2") (pinfunction "1Q_2") (pintype "output"))
      (node (ref "U2") (pin "4") (pinfunction "1D_4") (pintype "input"))
      (node (ref "U4") (pin "4") (pinfunction "1D_4") (pintype "input"))
      (node (ref "U5") (pin "4") (pinfunction "1D_4") (pintype "input"))
      (node (ref "U6") (pin "4") (pinfunction "1D_4") (pintype "input"))
      (node (ref "U7") (pin "4") (pinfunction "1D_4") (pintype "input"))
    )
    (net (code "54") (name "/KEYPAD_IN1") (class "Default")
      (node (ref "U1") (pin "5") (pinfunction "2D_5") (pintype "input"))
      (node (ref "U11") (pin "7") (pinfunction "2Q_7") (pintype "output"))
      (node (ref "U2") (pin "5") (pinfunction "2D_5") (pintype "input"))
      (node (ref "U4") (pin "5") (pinfunction "2D_5") (pintype "input"))
      (node (ref "U5") (pin "5") (pinfunction "2D_5") (pintype "input"))
      (node (ref "U6") (pin "5") (pinfunction "2D_5") (pintype "input"))
      (node (ref "U7") (pin "5") (pinfunction "2D_5") (pintype "input"))
    )
    (net (code "55") (name "/KEYPAD_IN2") (class "Default")
      (node (ref "U1") (pin "12") (pinfunction "3D_12") (pintype "input"))
      (node (ref "U11") (pin "10") (pinfunction "3Q_10") (pintype "output"))
      (node (ref "U2") (pin "12") (pinfunction "3D_12") (pintype "input"))
      (node (ref "U4") (pin "12") (pinfunction "3D_12") (pintype "input"))
      (node (ref "U5") (pin "12") (pinfunction "3D_12") (pintype "input"))
      (node (ref "U6") (pin "12") (pinfunction "3D_12") (pintype "input"))
      (node (ref "U7") (pin "12") (pinfunction "3D_12") (pintype "input"))
    )
    (net (code "56") (name "/KEYPAD_IN3") (class "Default")
      (node (ref "U1") (pin "13") (pinfunction "4D_13") (pintype "input"))
      (node (ref "U11") (pin "15") (pinfunction "4Q_15") (pintype "output"))
      (node (ref "U2") (pin "13") (pinfunction "4D_13") (pintype "input"))
      (node (ref "U4") (pin "13") (pinfunction "4D_13") (pintype "input"))
      (node (ref "U5") (pin "13") (pinfunction "4D_13") (pintype "input"))
      (node (ref "U6") (pin "13") (pinfunction "4D_13") (pintype "input"))
      (node (ref "U7") (pin "13") (pinfunction "4D_13") (pintype "input"))
    )
    (net (code "58") (name "/KEYPAD_SIGNAL") (class "Default")
      (node (ref "IC3") (pin "3") (pinfunction "CLK_3") (pintype "input"))
      (node (ref "Q1") (pin "2") (pinfunction "C_2") (pintype "passive"))
      (node (ref "R1") (pin "2") (pinfunction "2_2") (pintype "passive"))
      (node (ref "U11") (pin "9") (pinfunction "CLK_9") (pintype "input"))
    )
    (net (code "60") (name "/MEMORY1_1") (class "Default")
      (node (ref "IC6") (pin "9") (pinfunction "B0_9") (pintype "input"))
      (node (ref "U1") (pin "2") (pinfunction "1Q_2") (pintype "output"))
    )
    (net (code "61") (name "/MEMORY1_2") (class "Default")
      (node (ref "IC6") (pin "11") (pinfunction "B1_11") (pintype "input"))
      (node (ref "U1") (pin "7") (pinfunction "2Q_7") (pintype "output"))
    )
    (net (code "62") (name "/MEMORY1_3") (class "Default")
      (node (ref "IC6") (pin "14") (pinfunction "B2_14") (pintype "input"))
      (node (ref "U1") (pin "10") (pinfunction "3Q_10") (pintype "output"))
    )
    (net (code "63") (name "/MEMORY1_4") (class "Default")
      (node (ref "IC6") (pin "1") (pinfunction "B3_1") (pintype "input"))
      (node (ref "U1") (pin "15") (pinfunction "4Q_15") (pintype "output"))
    )
    (net (code "65") (name "/MEMORY2_1") (class "Default")
      (node (ref "IC8") (pin "9") (pinfunction "B0_9") (pintype "input"))
      (node (ref "U4") (pin "2") (pinfunction "1Q_2") (pintype "output"))
    )
    (net (code "66") (name "/MEMORY2_2") (class "Default")
      (node (ref "IC8") (pin "11") (pinfunction "B1_11") (pintype "input"))
      (node (ref "U4") (pin "7") (pinfunction "2Q_7") (pintype "output"))
    )
    (net (code "67") (name "/MEMORY2_3") (class "Default")
      (node (ref "IC8") (pin "14") (pinfunction "B2_14") (pintype "input"))
      (node (ref "U4") (pin "10") (pinfunction "3Q_10") (pintype "output"))
    )
    (net (code "68") (name "/MEMORY2_4") (class "Default")
      (node (ref "IC8") (pin "1") (pinfunction "B3_1") (pintype "input"))
      (node (ref "U4") (pin "15") (pinfunction "4Q_15") (pintype "output"))
    )
    (net (code "70") (name "/MEMORY3_1") (class "Default")
      (node (ref "IC9") (pin "9") (pinfunction "B0_9") (pintype "input"))
      (node (ref "U6") (pin "2") (pinfunction "1Q_2") (pintype "output"))
    )
    (net (code "71") (name "/MEMORY3_2") (class "Default")
      (node (ref "IC9") (pin "11") (pinfunction "B1_11") (pintype "input"))
      (node (ref "U6") (pin "7") (pinfunction "2Q_7") (pintype "output"))
    )
    (net (code "72") (name "/MEMORY3_3") (class "Default")
      (node (ref "IC9") (pin "14") (pinfunction "B2_14") (pintype "input"))
      (node (ref "U6") (pin "10") (pinfunction "3Q_10") (pintype "output"))
    )
    (net (code "73") (name "/MEMORY3_4") (class "Default")
      (node (ref "IC9") (pin "1") (pinfunction "B3_1") (pintype "input"))
      (node (ref "U6") (pin "15") (pinfunction "4Q_15") (pintype "output"))
    )
    (net (code "74") (name "/MEMORY_RESET") (class "Default")
      (node (ref "IC4") (pin "8") (pinfunction "O_8") (pintype "output"))
      (node (ref "U1") (pin "1") (pinfunction "~{CLR}_1") (pintype "input"))
      (node (ref "U4") (pin "1") (pinfunction "~{CLR}_1") (pintype "input"))
      (node (ref "U6") (pin "1") (pinfunction "~{CLR}_1") (pintype "input"))
    )
    (net (code "75") (name "/MEM_CLK1") (class "Default")
      (node (ref "IC2") (pin "3") (pinfunction "O_3") (pintype "output"))
      (node (ref "U1") (pin "9") (pinfunction "CLK_9") (pintype "input"))
    )
    (net (code "76") (name "/MEM_CLK2") (class "Default")
      (node (ref "IC2") (pin "6") (pinfunction "O_6") (pintype "output"))
      (node (ref "U4") (pin "9") (pinfunction "CLK_9") (pintype "input"))
    )
    (net (code "77") (name "/MEM_CLK3") (class "Default")
      (node (ref "IC2") (pin "8") (pinfunction "O_8") (pintype "output"))
      (node (ref "U6") (pin "9") (pinfunction "CLK_9") (pintype "input"))
    )
    (net (code "78") (name "/MODE") (class "Default")
      (node (ref "IC4") (pin "2") (pinfunction "B_2") (pintype "input"))
      (node (ref "R46") (pin "1") (pinfunction "1_1") (pintype "passive"))
      (node (ref "SD1") (pin "1") (pinfunction "A1_1") (pintype "passive"))
      (node (ref "U3") (pin "2") (pinfunction "1B_2") (pintype "input"))
    )
    (net (code "79") (name "/NUM0") (class "Default")
      (node (ref "D5") (pin "1") (pinfunction "A_1") (pintype "passive"))
      (node (ref "R39") (pin "2") (pinfunction "2_2") (pintype "passive"))
      (node (ref "SW0") (pin "2") (pinfunction "2_2") (pintype "passive"))
    )
    (net (code "80") (name "/NUM1") (class "Default")
      (node (ref "IC11") (pin "11") (pinfunction "I1_11") (pintype "input"))
      (node (ref "R7") (pin "1") (pinfunction "1_1") (pintype "passive"))
      (node (ref "SW1") (pin "2") (pinfunction "2_2") (pintype "passive"))
    )
    (net (code "81") (name "/NUM2") (class "Default")
      (node (ref "IC11") (pin "12") (pinfunction "I2_12") (pintype "input"))
      (node (ref "R8") (pin "1") (pinfunction "1_1") (pintype "passive"))
      (node (ref "SW2") (pin "2") (pinfunction "2_2") (pintype "passive"))
    )
    (net (code "82") (name "/NUM3") (class "Default")
      (node (ref "IC11") (pin "13") (pinfunction "I3_13") (pintype "input"))
      (node (ref "R9") (pin "1") (pinfunction "1_1") (pintype "passive"))
      (node (ref "SW3") (pin "2") (pinfunction "2_2") (pintype "passive"))
    )
    (net (code "83") (name "/NUM4") (class "Default")
      (node (ref "IC11") (pin "1") (pinfunction "I4_1") (pintype "input"))
      (node (ref "R17") (pin "1") (pinfunction "1_1") (pintype "passive"))
      (node (ref "SW4") (pin "2") (pinfunction "2_2") (pintype "passive"))
    )
    (net (code "84") (name "/NUM5") (class "Default")
      (node (ref "IC11") (pin "2") (pinfunction "I5_2") (pintype "input"))
      (node (ref "R18") (pin "1") (pinfunction "1_1") (pintype "passive"))
      (node (ref "SW5") (pin "2") (pinfunction "2_2") (pintype "passive"))
    )
    (net (code "85") (name "/NUM6") (class "Default")
      (node (ref "IC11") (pin "3") (pinfunction "I6_3") (pintype "input"))
      (node (ref "R19") (pin "1") (pinfunction "1_1") (pintype "passive"))
      (node (ref "SW6") (pin "2") (pinfunction "2_2") (pintype "passive"))
    )
    (net (code "86") (name "/NUM7") (class "Default")
      (node (ref "IC11") (pin "4") (pinfunction "I7_4") (pintype "input"))
      (node (ref "R23") (pin "1") (pinfunction "1_1") (pintype "passive"))
      (node (ref "SW7") (pin "2") (pinfunction "2_2") (pintype "passive"))
    )
    (net (code "87") (name "/NUM8") (class "Default")
      (node (ref "IC11") (pin "5") (pinfunction "I8_5") (pintype "input"))
      (node (ref "R24") (pin "1") (pinfunction "1_1") (pintype "passive"))
      (node (ref "SW8") (pin "2") (pinfunction "2_2") (pintype "passive"))
    )
    (net (code "88") (name "/NUM9") (class "Default")
      (node (ref "IC11") (pin "10") (pinfunction "I9_10") (pintype "input"))
      (node (ref "R25") (pin "1") (pinfunction "1_1") (pintype "passive"))
      (node (ref "SW9") (pin "2") (pinfunction "2_2") (pintype "passive"))
    )
    (net (code "89") (name "/RESET") (class "Default")
      (node (ref "R32") (pin "1") (pinfunction "1_1") (pintype "passive"))
      (node (ref "SW12") (pin "2") (pinfunction "2_2") (pintype "passive"))
      (node (ref "U3") (pin "5") (pinfunction "2C_5") (pintype "input"))
    )
    (net (code "90") (name "/RESET_SIGNAL") (class "Default")
      (node (ref "IC4") (pin "4") (pinfunction "A_4") (pintype "input"))
      (node (ref "U2") (pin "1") (pinfunction "~{CLR}_1") (pintype "input"))
      (node (ref "U3") (pin "6") (pinfunction "2Y_6") (pintype "output"))
      (node (ref "U5") (pin "1") (pinfunction "~{CLR}_1") (pintype "input"))
      (node (ref "U7") (pin "1") (pinfunction "~{CLR}_1") (pintype "input"))
      (node (ref "U8") (pin "9") (pinfunction "4A_9") (pintype "input"))
    )
    (net (code "91") (name "/SELECT1") (class "Default")
      (node (ref "IC1") (pin "15") (pinfunction "~{Y}0_15") (pintype "output"))
      (node (ref "U2") (pin "9") (pinfunction "CLK_9") (pintype "input"))
      (node (ref "U8") (pin "1") (pinfunction "1A_1") (pintype "input"))
    )
    (net (code "92") (name "/SELECT2") (class "Default")
      (node (ref "IC1") (pin "14") (pinfunction "~{Y}1_14") (pintype "output"))
      (node (ref "U5") (pin "9") (pinfunction "CLK_9") (pintype "input"))
      (node (ref "U8") (pin "3") (pinfunction "2A_3") (pintype "input"))
    )
    (net (code "93") (name "/SELECT3") (class "Default")
      (node (ref "IC1") (pin "13") (pinfunction "~{Y}2_13") (pintype "output"))
      (node (ref "U7") (pin "9") (pinfunction "CLK_9") (pintype "input"))
      (node (ref "U8") (pin "5") (pinfunction "3A_5") (pintype "input"))
    )
    (net (code "94") (name "/SENSOR_SIGNAL") (class "Default")
      (node (ref "U3") (pin "3") (pinfunction "2A_3") (pintype "input"))
      (node (ref "U9") (pin "1") (pinfunction "OUT1_1") (pintype "output"))
    )
    (net (code "95") (name "/VALID_PASS") (class "Default")
      (node (ref "IC4") (pin "1") (pinfunction "A_1") (pintype "input"))
      (node (ref "IC9") (pin "6") (pinfunction "A=Bout_6") (pintype "output"))
      (node (ref "R14") (pin "2") (pinfunction "2_2") (pintype "passive"))
      (node (ref "R20") (pin "2") (pinfunction "2_2") (pintype "passive"))
    )
    (net (code "96") (name "GND") (class "Default")
      (node (ref "C1") (pin "1") (pinfunction "1_1") (pintype "passive"))
      (node (ref "C2") (pin "2") (pinfunction "2_2") (pintype "passive"))
      (node (ref "C3") (pin "2") (pinfunction "2_2") (pintype "passive"))
      (node (ref "C4") (pin "1") (pinfunction "1_1") (pintype "passive"))
      (node (ref "D10") (pin "1") (pinfunction "A_1") (pintype "passive"))
      (node (ref "D13") (pin "C") (pinfunction "C_C") (pintype "passive"))
      (node (ref "IC1") (pin "3") (pinfunction "C_3") (pintype "input"))
      (node (ref "IC1") (pin "4") (pinfunction "~{G}2A_4") (pintype "input"))
      (node (ref "IC1") (pin "5") (pinfunction "~{G}2B_5") (pintype "input"))
      (node (ref "IC1") (pin "8") (pinfunction "GND_8") (pintype "power_in"))
      (node (ref "IC10") (pin "8") (pinfunction "GND_8") (pintype "power_in"))
      (node (ref "IC11") (pin "8") (pinfunction "GND_8") (pintype "power_in"))
      (node (ref "IC12") (pin "2") (pinfunction "GND_2") (pintype "passive"))
      (node (ref "IC2") (pin "7") (pinfunction "GND_7") (pintype "power_in"))
      (node (ref "IC3") (pin "7") (pinfunction "GND_7") (pintype "power_in"))
      (node (ref "IC4") (pin "7") (pinfunction "GND_7") (pintype "power_in"))
      (node (ref "IC5") (pin "8") (pinfunction "GND_8") (pintype "power_in"))
      (node (ref "IC6") (pin "2") (pinfunction "A<Bin_2") (pintype "input"))
      (node (ref "IC6") (pin "4") (pinfunction "A>Bin_4") (pintype "input"))
      (node (ref "IC6") (pin "8") (pinfunction "GND_8") (pintype "power_in"))
      (node (ref "IC7") (pin "8") (pinfunction "GND_8") (pintype "power_in"))
      (node (ref "IC8") (pin "8") (pinfunction "GND_8") (pintype "power_in"))
      (node (ref "IC9") (pin "8") (pinfunction "GND_8") (pintype "power_in"))
      (node (ref "JP2") (pin "1") (pinfunction "1_1") (pintype "passive"))
      (node (ref "LED1") (pin "2") (pinfunction "2_2") (pintype "passive"))
      (node (ref "ON/OFF1") (pin "2") (pinfunction "TN_2") (pintype "passive"))
      (node (ref "Q1") (pin "1") (pinfunction "E_1") (pintype "passive"))
      (node (ref "Q3") (pin "1") (pinfunction "E_1") (pintype "passive"))
      (node (ref "Q4") (pin "1") (pinfunction "E_1") (pintype "passive"))
      (node (ref "R10") (pin "1") (pinfunction "1_1") (pintype "passive"))
      (node (ref "R11") (pin "1") (pinfunction "1_1") (pintype "passive"))
      (node (ref "R13") (pin "1") (pinfunction "1_1") (pintype "passive"))
      (node (ref "R3") (pin "2") (pinfunction "2_2") (pintype "passive"))
      (node (ref "R39") (pin "1") (pinfunction "1_1") (pintype "passive"))
      (node (ref "R40") (pin "1") (pinfunction "1_1") (pintype "passive"))
      (node (ref "R44") (pin "CCW") (pinfunction "1_CCW") (pintype "passive"))
      (node (ref "R46") (pin "2") (pinfunction "2_2") (pintype "passive"))
      (node (ref "R5") (pin "2") (pinfunction "2_2") (pintype "passive"))
      (node (ref "RL2") (pin "4") (pinfunction "4_4") (pintype "passive"))
      (node (ref "SW1") (pin "1") (pinfunction "1_1") (pintype "passive"))
      (node (ref "SW12") (pin "1") (pinfunction "1_1") (pintype "passive"))
      (node (ref "SW2") (pin "1") (pinfunction "1_1") (pintype "passive"))
      (node (ref "SW3") (pin "1") (pinfunction "1_1") (pintype "passive"))
      (node (ref "SW4") (pin "1") (pinfunction "1_1") (pintype "passive"))
      (node (ref "SW5") (pin "1") (pinfunction "1_1") (pintype "passive"))
      (node (ref "SW6") (pin "1") (pinfunction "1_1") (pintype "passive"))
      (node (ref "SW7") (pin "1") (pinfunction "1_1") (pintype "passive"))
      (node (ref "SW8") (pin "1") (pinfunction "1_1") (pintype "passive"))
      (node (ref "SW9") (pin "1") (pinfunction "1_1") (pintype "passive"))
      (node (ref "U1") (pin "8") (pinfunction "GND_8") (pintype "power_in"))
      (node (ref "U10") (pin "7") (pinfunction "GND_7") (pintype "power_in"))
      (node (ref "U11") (pin "8") (pinfunction "GND_8") (pintype "power_in"))
      (node (ref "U2") (pin "8") (pinfunction "GND_8") (pintype "power_in"))
      (node (ref "U3") (pin "7") (pinfunction "GND_7") (pintype "power_in"))
      (node (ref "U4") (pin "8") (pinfunction "GND_8") (pintype "power_in"))
      (node (ref "U5") (pin "8") (pinfunction "GND_8") (pintype "power_in"))
      (node (ref "U6") (pin "8") (pinfunction "GND_8") (pintype "power_in"))
      (node (ref "U7") (pin "8") (pinfunction "GND_8") (pintype "power_in"))
      (node (ref "U8") (pin "7") (pinfunction "GND_7") (pintype "power_in"))
      (node (ref "U9") (pin "4") (pinfunction "GND_4") (pintype "power_in"))
    )
    (net (code "97") (name "Net-(D1-K)") (class "Default")
      (node (ref "D1") (pin "2") (pinfunction "K_2") (pintype "passive"))
      (node (ref "D2") (pin "2") (pinfunction "K_2") (pintype "passive"))
      (node (ref "D3") (pin "2") (pinfunction "K_2") (pintype "passive"))
      (node (ref "D4") (pin "2") (pinfunction "K_2") (pintype "passive"))
      (node (ref "D5") (pin "2") (pinfunction "K_2") (pintype "passive"))
      (node (ref "R2") (pin "1") (pinfunction "1_1") (pintype "passive"))
      (node (ref "R3") (pin "1") (pinfunction "1_1") (pintype "passive"))
    )
    (net (code "98") (name "Net-(D6-A)") (class "Default")
      (node (ref "D6") (pin "1") (pinfunction "A_1") (pintype "passive"))
      (node (ref "RL2") (pin "1") (pinfunction "1_1") (pintype "passive"))
    )
    (net (code "99") (name "Net-(D6-K)") (class "Default")
      (node (ref "C3") (pin "1") (pinfunction "1_1") (pintype "passive"))
      (node (ref "C4") (pin "2") (pinfunction "2_2") (pintype "passive"))
      (node (ref "D6") (pin "2") (pinfunction "K_2") (pintype "passive"))
      (node (ref "IC12") (pin "1") (pinfunction "IN_1") (pintype "passive"))
    )
    (net (code "100") (name "Net-(D7-A)") (class "Default")
      (node (ref "D7") (pin "1") (pinfunction "A_1") (pintype "passive"))
      (node (ref "IC3") (pin "11") (pinfunction "CLK_11") (pintype "input"))
      (node (ref "IC3") (pin "2") (pinfunction "D_2") (pintype "input"))
      (node (ref "IC3") (pin "6") (pinfunction "~{Q}_6") (pintype "output"))
    )
    (net (code "101") (name "Net-(D7-K)") (class "Default")
      (node (ref "D7") (pin "2") (pinfunction "K_2") (pintype "passive"))
      (node (ref "D8") (pin "2") (pinfunction "K_2") (pintype "passive"))
      (node (ref "IC4") (pin "5") (pinfunction "B_5") (pintype "input"))
      (node (ref "R5") (pin "1") (pinfunction "1_1") (pintype "passive"))
    )
    (net (code "102") (name "Net-(D8-A)") (class "Default")
      (node (ref "D8") (pin "1") (pinfunction "A_1") (pintype "passive"))
      (node (ref "IC3") (pin "12") (pinfunction "D_12") (pintype "input"))
      (node (ref "IC3") (pin "8") (pinfunction "~{Q}_8") (pintype "output"))
    )
    (net (code "103") (name "Net-(D9-A)") (class "Default")
      (node (ref "D9") (pin "1") (pinfunction "A_1") (pintype "passive"))
      (node (ref "Q4") (pin "2") (pinfunction "C_2") (pintype "passive"))
      (node (ref "R12") (pin "2") (pinfunction "2_2") (pintype "passive"))
      (node (ref "RL1") (pin "4") (pinfunction "4_4") (pintype "passive"))
    )
    (net (code "104") (name "Net-(D10-K)") (class "Default")
      (node (ref "D10") (pin "2") (pinfunction "K_2") (pintype "passive"))
      (node (ref "R34") (pin "1") (pinfunction "1_1") (pintype "passive"))
      (node (ref "U9") (pin "3") (pinfunction "+IN1_3") (pintype "input"))
    )
    (net (code "105") (name "Net-(D13-PadA)") (class "Default")
      (node (ref "D13") (pin "A") (pinfunction "A_A") (pintype "passive"))
      (node (ref "R35") (pin "1") (pinfunction "1_1") (pintype "passive"))
    )
    (net (code "106") (name "Net-(DS3-K-Pad3)") (class "Default")
      (node (ref "DS3") (pin "3") (pinfunction "K_3") (pintype "passive"))
      (node (ref "DS3") (pin "8") (pinfunction "K_8") (pintype "passive"))
      (node (ref "R10") (pin "2") (pinfunction "2_2") (pintype "passive"))
    )
    (net (code "107") (name "Net-(DS3-a)") (class "Default")
      (node (ref "DS3") (pin "7") (pinfunction "a_7") (pintype "passive"))
      (node (ref "IC5") (pin "13") (pinfunction "~{a}_13") (pintype "open_collector"))
    )
    (net (code "108") (name "Net-(DS3-b)") (class "Default")
      (node (ref "DS3") (pin "6") (pinfunction "b_6") (pintype "passive"))
      (node (ref "IC5") (pin "12") (pinfunction "~{b}_12") (pintype "open_collector"))
    )
    (net (code "109") (name "Net-(DS3-c)") (class "Default")
      (node (ref "DS3") (pin "4") (pinfunction "c_4") (pintype "passive"))
      (node (ref "IC5") (pin "11") (pinfunction "~{c}_11") (pintype "open_collector"))
    )
    (net (code "110") (name "Net-(DS3-d)") (class "Default")
      (node (ref "DS3") (pin "2") (pinfunction "d_2") (pintype "passive"))
      (node (ref "IC5") (pin "10") (pinfunction "~{d}_10") (pintype "open_collector"))
    )
    (net (code "111") (name "Net-(DS3-e)") (class "Default")
      (node (ref "DS3") (pin "1") (pinfunction "e_1") (pintype "passive"))
      (node (ref "IC5") (pin "9") (pinfunction "~{e}_9") (pintype "open_collector"))
    )
    (net (code "112") (name "Net-(DS3-f)") (class "Default")
      (node (ref "DS3") (pin "9") (pinfunction "f_9") (pintype "passive"))
      (node (ref "IC5") (pin "15") (pinfunction "~{f}_15") (pintype "open_collector"))
    )
    (net (code "113") (name "Net-(DS3-g)") (class "Default")
      (node (ref "DS3") (pin "10") (pinfunction "g_10") (pintype "passive"))
      (node (ref "IC5") (pin "14") (pinfunction "~{g}_14") (pintype "open_collector"))
    )
    (net (code "114") (name "Net-(DS4-K-Pad3)") (class "Default")
      (node (ref "DS4") (pin "3") (pinfunction "K_3") (pintype "passive"))
      (node (ref "DS4") (pin "8") (pinfunction "K_8") (pintype "passive"))
      (node (ref "R11") (pin "2") (pinfunction "2_2") (pintype "passive"))
    )
    (net (code "115") (name "Net-(DS4-a)") (class "Default")
      (node (ref "DS4") (pin "7") (pinfunction "a_7") (pintype "passive"))
      (node (ref "IC7") (pin "13") (pinfunction "~{a}_13") (pintype "open_collector"))
    )
    (net (code "116") (name "Net-(DS4-b)") (class "Default")
      (node (ref "DS4") (pin "6") (pinfunction "b_6") (pintype "passive"))
      (node (ref "IC7") (pin "12") (pinfunction "~{b}_12") (pintype "open_collector"))
    )
    (net (code "117") (name "Net-(DS4-c)") (class "Default")
      (node (ref "DS4") (pin "4") (pinfunction "c_4") (pintype "passive"))
      (node (ref "IC7") (pin "11") (pinfunction "~{c}_11") (pintype "open_collector"))
    )
    (net (code "118") (name "Net-(DS4-d)") (class "Default")
      (node (ref "DS4") (pin "2") (pinfunction "d_2") (pintype "passive"))
      (node (ref "IC7") (pin "10") (pinfunction "~{d}_10") (pintype "open_collector"))
    )
    (net (code "119") (name "Net-(DS4-e)") (class "Default")
      (node (ref "DS4") (pin "1") (pinfunction "e_1") (pintype "passive"))
      (node (ref "IC7") (pin "9") (pinfunction "~{e}_9") (pintype "open_collector"))
    )
    (net (code "120") (name "Net-(DS4-f)") (class "Default")
      (node (ref "DS4") (pin "9") (pinfunction "f_9") (pintype "passive"))
      (node (ref "IC7") (pin "15") (pinfunction "~{f}_15") (pintype "open_collector"))
    )
    (net (code "121") (name "Net-(DS4-g)") (class "Default")
      (node (ref "DS4") (pin "10") (pinfunction "g_10") (pintype "passive"))
      (node (ref "IC7") (pin "14") (pinfunction "~{g}_14") (pintype "open_collector"))
    )
    (net (code "122") (name "Net-(DS5-K-Pad3)") (class "Default")
      (node (ref "DS5") (pin "3") (pinfunction "K_3") (pintype "passive"))
      (node (ref "DS5") (pin "8") (pinfunction "K_8") (pintype "passive"))
      (node (ref "R13") (pin "2") (pinfunction "2_2") (pintype "passive"))
    )
    (net (code "123") (name "Net-(DS5-a)") (class "Default")
      (node (ref "DS5") (pin "7") (pinfunction "a_7") (pintype "passive"))
      (node (ref "IC10") (pin "13") (pinfunction "~{a}_13") (pintype "open_collector"))
    )
    (net (code "124") (name "Net-(DS5-b)") (class "Default")
      (node (ref "DS5") (pin "6") (pinfunction "b_6") (pintype "passive"))
      (node (ref "IC10") (pin "12") (pinfunction "~{b}_12") (pintype "open_collector"))
    )
    (net (code "125") (name "Net-(DS5-c)") (class "Default")
      (node (ref "DS5") (pin "4") (pinfunction "c_4") (pintype "passive"))
      (node (ref "IC10") (pin "11") (pinfunction "~{c}_11") (pintype "open_collector"))
    )
    (net (code "126") (name "Net-(DS5-d)") (class "Default")
      (node (ref "DS5") (pin "2") (pinfunction "d_2") (pintype "passive"))
      (node (ref "IC10") (pin "10") (pinfunction "~{d}_10") (pintype "open_collector"))
    )
    (net (code "127") (name "Net-(DS5-e)") (class "Default")
      (node (ref "DS5") (pin "1") (pinfunction "e_1") (pintype "passive"))
      (node (ref "IC10") (pin "9") (pinfunction "~{e}_9") (pintype "open_collector"))
    )
    (net (code "128") (name "Net-(DS5-f)") (class "Default")
      (node (ref "DS5") (pin "9") (pinfunction "f_9") (pintype "passive"))
      (node (ref "IC10") (pin "15") (pinfunction "~{f}_15") (pintype "open_collector"))
    )
    (net (code "129") (name "Net-(DS5-g)") (class "Default")
      (node (ref "DS5") (pin "10") (pinfunction "g_10") (pintype "passive"))
      (node (ref "IC10") (pin "14") (pinfunction "~{g}_14") (pintype "open_collector"))
    )
    (net (code "130") (name "Net-(HD1-Pad1)") (class "Default")
      (node (ref "HD1") (pin "1") (pinfunction "1_1") (pintype "passive"))
      (node (ref "RL1") (pin "2") (pinfunction "2_2") (pintype "passive"))
    )
    (net (code "131") (name "Net-(HD1-Pad2)") (class "Default")
      (node (ref "HD1") (pin "2") (pinfunction "2_2") (pintype "passive"))
      (node (ref "RL1") (pin "1") (pinfunction "1_1") (pintype "passive"))
    )
    (net (code "132") (name "Net-(HD1-Pad3)") (class "Default")
      (node (ref "HD1") (pin "3") (pinfunction "3_3") (pintype "passive"))
      (node (ref "RL1") (pin "3") (pinfunction "3_3") (pintype "passive"))
    )
    (net (code "133") (name "Net-(IC1-A)") (class "Default")
      (node (ref "IC1") (pin "1") (pinfunction "A_1") (pintype "input"))
      (node (ref "IC3") (pin "5") (pinfunction "Q_5") (pintype "output"))
    )
    (net (code "134") (name "Net-(IC1-B)") (class "Default")
      (node (ref "IC1") (pin "2") (pinfunction "B_2") (pintype "input"))
      (node (ref "IC3") (pin "9") (pinfunction "Q_9") (pintype "output"))
    )
    (net (code "135") (name "Net-(IC2A-A)") (class "Default")
      (node (ref "IC2") (pin "1") (pinfunction "A_1") (pintype "input"))
      (node (ref "U8") (pin "2") (pinfunction "1Y_2") (pintype "output"))
    )
    (net (code "136") (name "Net-(IC2B-A)") (class "Default")
      (node (ref "IC2") (pin "4") (pinfunction "A_4") (pintype "input"))
      (node (ref "U8") (pin "4") (pinfunction "2Y_4") (pintype "output"))
    )
    (net (code "137") (name "Net-(IC2C-A)") (class "Default")
      (node (ref "IC2") (pin "10") (pinfunction "A_10") (pintype "input"))
      (node (ref "U8") (pin "6") (pinfunction "3Y_6") (pintype "output"))
    )
    (net (code "138") (name "Net-(IC3A-CLR)") (class "Default")
      (node (ref "IC3") (pin "1") (pinfunction "CLR_1") (pintype "input"))
      (node (ref "IC3") (pin "13") (pinfunction "CLR_13") (pintype "input"))
      (node (ref "IC4") (pin "6") (pinfunction "O_6") (pintype "output"))
    )
    (net (code "139") (name "Net-(IC8-A<Bout)") (class "Default")
      (node (ref "IC8") (pin "7") (pinfunction "A<Bout_7") (pintype "output"))
      (node (ref "IC9") (pin "2") (pinfunction "A<Bin_2") (pintype "input"))
    )
    (net (code "140") (name "Net-(IC8-A=Bout)") (class "Default")
      (node (ref "IC8") (pin "6") (pinfunction "A=Bout_6") (pintype "output"))
      (node (ref "IC9") (pin "3") (pinfunction "A=Bin_3") (pintype "input"))
    )
    (net (code "141") (name "Net-(IC8-A>Bout)") (class "Default")
      (node (ref "IC8") (pin "5") (pinfunction "A>Bout_5") (pintype "output"))
      (node (ref "IC9") (pin "4") (pinfunction "A>Bin_4") (pintype "input"))
    )
    (net (code "142") (name "Net-(IC11-A)") (class "Default")
      (node (ref "IC11") (pin "9") (pinfunction "A_9") (pintype "output"))
      (node (ref "U10") (pin "1") (pinfunction "1A_1") (pintype "input"))
    )
    (net (code "143") (name "Net-(IC11-B)") (class "Default")
      (node (ref "IC11") (pin "7") (pinfunction "B_7") (pintype "output"))
      (node (ref "U10") (pin "3") (pinfunction "2A_3") (pintype "input"))
    )
    (net (code "144") (name "Net-(IC11-C)") (class "Default")
      (node (ref "IC11") (pin "6") (pinfunction "C_6") (pintype "output"))
      (node (ref "U10") (pin "5") (pinfunction "3A_5") (pintype "input"))
    )
    (net (code "145") (name "Net-(IC11-D)") (class "Default")
      (node (ref "IC11") (pin "14") (pinfunction "D_14") (pintype "output"))
      (node (ref "U10") (pin "9") (pinfunction "4A_9") (pintype "input"))
    )
    (net (code "146") (name "Net-(JP2-Pad2)") (class "Default")
      (node (ref "JP2") (pin "2") (pinfunction "2_2") (pintype "passive"))
      (node (ref "RL2") (pin "2") (pinfunction "2_2") (pintype "passive"))
    )
    (net (code "147") (name "Net-(LED1-Pad1)") (class "Default")
      (node (ref "LED1") (pin "1") (pinfunction "1_1") (pintype "passive"))
      (node (ref "R4") (pin "1") (pinfunction "1_1") (pintype "passive"))
    )
    (net (code "148") (name "Net-(LED2-Pad1)") (class "Default")
      (node (ref "LED2") (pin "1") (pinfunction "1_1") (pintype "passive"))
      (node (ref "R6") (pin "2") (pinfunction "2_2") (pintype "passive"))
    )
    (net (code "149") (name "Net-(ON/OFF1-T)") (class "Default")
      (node (ref "ON/OFF1") (pin "1") (pinfunction "T_1") (pintype "passive"))
      (node (ref "RL2") (pin "3") (pinfunction "3_3") (pintype "passive"))
      (node (ref "RL2") (pin "5") (pinfunction "5_5") (pintype "passive"))
    )
    (net (code "150") (name "Net-(Q1-B)") (class "Default")
      (node (ref "Q1") (pin "3") (pinfunction "B_3") (pintype "passive"))
      (node (ref "R2") (pin "2") (pinfunction "2_2") (pintype "passive"))
    )
    (net (code "151") (name "Net-(Q3-B)") (class "Default")
      (node (ref "Q3") (pin "3") (pinfunction "B_3") (pintype "passive"))
      (node (ref "R14") (pin "1") (pinfunction "1_1") (pintype "passive"))
    )
    (net (code "152") (name "Net-(Q3-C)") (class "Default")
      (node (ref "LED2") (pin "2") (pinfunction "2_2") (pintype "passive"))
      (node (ref "Q3") (pin "2") (pinfunction "C_2") (pintype "passive"))
    )
    (net (code "153") (name "Net-(Q4-B)") (class "Default")
      (node (ref "Q4") (pin "3") (pinfunction "B_3") (pintype "passive"))
      (node (ref "R20") (pin "1") (pinfunction "1_1") (pintype "passive"))
    )
    (net (code "154") (name "Net-(R44-2)") (class "Default")
      (node (ref "R44") (pin "W") (pinfunction "2_W") (pintype "passive"))
      (node (ref "U9") (pin "2") (pinfunction "-IN1_2") (pintype "input"))
    )
    (net (code "155") (name "unconnected-(DS3-DP-Pad5)") (class "Default")
      (node (ref "DS3") (pin "5") (pinfunction "DP_5") (pintype "passive"))
    )
    (net (code "156") (name "unconnected-(DS4-DP-Pad5)") (class "Default")
      (node (ref "DS4") (pin "5") (pinfunction "DP_5") (pintype "passive"))
    )
    (net (code "157") (name "unconnected-(DS5-DP-Pad5)") (class "Default")
      (node (ref "DS5") (pin "5") (pinfunction "DP_5") (pintype "passive"))
    )
    (net (code "158") (name "unconnected-(IC1-~{Y}3-Pad12)") (class "Default")
      (node (ref "IC1") (pin "12") (pinfunction "~{Y}3_12") (pintype "output"))
    )
    (net (code "159") (name "unconnected-(IC1-~{Y}4-Pad11)") (class "Default")
      (node (ref "IC1") (pin "11") (pinfunction "~{Y}4_11") (pintype "output"))
    )
    (net (code "160") (name "unconnected-(IC1-~{Y}5-Pad10)") (class "Default")
      (node (ref "IC1") (pin "10") (pinfunction "~{Y}5_10") (pintype "output"))
    )
    (net (code "161") (name "unconnected-(IC1-~{Y}6-Pad9)") (class "Default")
      (node (ref "IC1") (pin "9") (pinfunction "~{Y}6_9") (pintype "output"))
    )
    (net (code "162") (name "unconnected-(IC1-~{Y}7-Pad7)") (class "Default")
      (node (ref "IC1") (pin "7") (pinfunction "~{Y}7_7") (pintype "output"))
    )
    (net (code "163") (name "unconnected-(IC3A-PR-Pad4)") (class "Default")
      (node (ref "IC3") (pin "4") (pinfunction "PR_4") (pintype "input+no_connect"))
    )
    (net (code "164") (name "unconnected-(IC3B-PR-Pad10)") (class "Default")
      (node (ref "IC3") (pin "10") (pinfunction "PR_10") (pintype "input+no_connect"))
    )
    (net (code "165") (name "unconnected-(IC9-A<Bout-Pad7)") (class "Default")
      (node (ref "IC9") (pin "7") (pinfunction "A<Bout_7") (pintype "output"))
    )
    (net (code "166") (name "unconnected-(IC9-A>Bout-Pad5)") (class "Default")
      (node (ref "IC9") (pin "5") (pinfunction "A>Bout_5") (pintype "output"))
    )
    (net (code "167") (name "unconnected-(ON/OFF1-S-Pad3)") (class "Default")
      (node (ref "ON/OFF1") (pin "3") (pinfunction "S_3") (pintype "power_in"))
    )
    (net (code "168") (name "unconnected-(U1-1~Q-Pad3)") (class "Default")
      (node (ref "U1") (pin "3") (pinfunction "1~Q_3") (pintype "output+no_connect"))
    )
    (net (code "169") (name "unconnected-(U1-2~Q-Pad6)") (class "Default")
      (node (ref "U1") (pin "6") (pinfunction "2~Q_6") (pintype "output+no_connect"))
    )
    (net (code "170") (name "unconnected-(U1-3~Q-Pad11)") (class "Default")
      (node (ref "U1") (pin "11") (pinfunction "3~Q_11") (pintype "output+no_connect"))
    )
    (net (code "171") (name "unconnected-(U1-4~Q-Pad14)") (class "Default")
      (node (ref "U1") (pin "14") (pinfunction "4~Q_14") (pintype "output+no_connect"))
    )
    (net (code "172") (name "unconnected-(U2-1~Q-Pad3)") (class "Default")
      (node (ref "U2") (pin "3") (pinfunction "1~Q_3") (pintype "output+no_connect"))
    )
    (net (code "173") (name "unconnected-(U2-2~Q-Pad6)") (class "Default")
      (node (ref "U2") (pin "6") (pinfunction "2~Q_6") (pintype "output+no_connect"))
    )
    (net (code "174") (name "unconnected-(U2-3~Q-Pad11)") (class "Default")
      (node (ref "U2") (pin "11") (pinfunction "3~Q_11") (pintype "output+no_connect"))
    )
    (net (code "175") (name "unconnected-(U2-4~Q-Pad14)") (class "Default")
      (node (ref "U2") (pin "14") (pinfunction "4~Q_14") (pintype "output+no_connect"))
    )
    (net (code "176") (name "unconnected-(U3-3A-Pad9)") (class "Default")
      (node (ref "U3") (pin "9") (pinfunction "3A_9") (pintype "input+no_connect"))
    )
    (net (code "177") (name "unconnected-(U3-3B-Pad10)") (class "Default")
      (node (ref "U3") (pin "10") (pinfunction "3B_10") (pintype "input+no_connect"))
    )
    (net (code "178") (name "unconnected-(U3-3C-Pad11)") (class "Default")
      (node (ref "U3") (pin "11") (pinfunction "3C_11") (pintype "input+no_connect"))
    )
    (net (code "179") (name "unconnected-(U3-3Y-Pad8)") (class "Default")
      (node (ref "U3") (pin "8") (pinfunction "3Y_8") (pintype "output"))
    )
    (net (code "180") (name "unconnected-(U4-1~Q-Pad3)") (class "Default")
      (node (ref "U4") (pin "3") (pinfunction "1~Q_3") (pintype "output+no_connect"))
    )
    (net (code "181") (name "unconnected-(U4-2~Q-Pad6)") (class "Default")
      (node (ref "U4") (pin "6") (pinfunction "2~Q_6") (pintype "output+no_connect"))
    )
    (net (code "182") (name "unconnected-(U4-3~Q-Pad11)") (class "Default")
      (node (ref "U4") (pin "11") (pinfunction "3~Q_11") (pintype "output+no_connect"))
    )
    (net (code "183") (name "unconnected-(U4-4~Q-Pad14)") (class "Default")
      (node (ref "U4") (pin "14") (pinfunction "4~Q_14") (pintype "output+no_connect"))
    )
    (net (code "184") (name "unconnected-(U5-1~Q-Pad3)") (class "Default")
      (node (ref "U5") (pin "3") (pinfunction "1~Q_3") (pintype "output+no_connect"))
    )
    (net (code "185") (name "unconnected-(U5-2~Q-Pad6)") (class "Default")
      (node (ref "U5") (pin "6") (pinfunction "2~Q_6") (pintype "output+no_connect"))
    )
    (net (code "186") (name "unconnected-(U5-3~Q-Pad11)") (class "Default")
      (node (ref "U5") (pin "11") (pinfunction "3~Q_11") (pintype "output+no_connect"))
    )
    (net (code "187") (name "unconnected-(U5-4~Q-Pad14)") (class "Default")
      (node (ref "U5") (pin "14") (pinfunction "4~Q_14") (pintype "output+no_connect"))
    )
    (net (code "188") (name "unconnected-(U6-1~Q-Pad3)") (class "Default")
      (node (ref "U6") (pin "3") (pinfunction "1~Q_3") (pintype "output+no_connect"))
    )
    (net (code "189") (name "unconnected-(U6-2~Q-Pad6)") (class "Default")
      (node (ref "U6") (pin "6") (pinfunction "2~Q_6") (pintype "output+no_connect"))
    )
    (net (code "190") (name "unconnected-(U6-3~Q-Pad11)") (class "Default")
      (node (ref "U6") (pin "11") (pinfunction "3~Q_11") (pintype "output+no_connect"))
    )
    (net (code "191") (name "unconnected-(U6-4~Q-Pad14)") (class "Default")
      (node (ref "U6") (pin "14") (pinfunction "4~Q_14") (pintype "output+no_connect"))
    )
    (net (code "192") (name "unconnected-(U7-1~Q-Pad3)") (class "Default")
      (node (ref "U7") (pin "3") (pinfunction "1~Q_3") (pintype "output+no_connect"))
    )
    (net (code "193") (name "unconnected-(U7-2~Q-Pad6)") (class "Default")
      (node (ref "U7") (pin "6") (pinfunction "2~Q_6") (pintype "output+no_connect"))
    )
    (net (code "194") (name "unconnected-(U7-3~Q-Pad11)") (class "Default")
      (node (ref "U7") (pin "11") (pinfunction "3~Q_11") (pintype "output+no_connect"))
    )
    (net (code "195") (name "unconnected-(U7-4~Q-Pad14)") (class "Default")
      (node (ref "U7") (pin "14") (pinfunction "4~Q_14") (pintype "output+no_connect"))
    )
    (net (code "196") (name "unconnected-(U8-6A-Pad13)") (class "Default")
      (node (ref "U8") (pin "13") (pinfunction "6A_13") (pintype "input+no_connect"))
    )
    (net (code "197") (name "unconnected-(U8-6Y-Pad12)") (class "Default")
      (node (ref "U8") (pin "12") (pinfunction "6Y_12") (pintype "output"))
    )
    (net (code "198") (name "unconnected-(U10-5A-Pad11)") (class "Default")
      (node (ref "U10") (pin "11") (pinfunction "5A_11") (pintype "input+no_connect"))
    )
    (net (code "199") (name "unconnected-(U10-5Y-Pad10)") (class "Default")
      (node (ref "U10") (pin "10") (pinfunction "5Y_10") (pintype "output"))
    )
    (net (code "200") (name "unconnected-(U10-6A-Pad13)") (class "Default")
      (node (ref "U10") (pin "13") (pinfunction "6A_13") (pintype "input+no_connect"))
    )
    (net (code "201") (name "unconnected-(U10-6Y-Pad12)") (class "Default")
      (node (ref "U10") (pin "12") (pinfunction "6Y_12") (pintype "output"))
    )
    (net (code "202") (name "unconnected-(U11-1~Q-Pad3)") (class "Default")
      (node (ref "U11") (pin "3") (pinfunction "1~Q_3") (pintype "output"))
    )
    (net (code "203") (name "unconnected-(U11-2~Q-Pad6)") (class "Default")
      (node (ref "U11") (pin "6") (pinfunction "2~Q_6") (pintype "output"))
    )
    (net (code "204") (name "unconnected-(U11-3~Q-Pad11)") (class "Default")
      (node (ref "U11") (pin "11") (pinfunction "3~Q_11") (pintype "output"))
    )
    (net (code "205") (name "unconnected-(U11-4~Q-Pad14)") (class "Default")
      (node (ref "U11") (pin "14") (pinfunction "4~Q_14") (pintype "output"))
    )
    (net (code "206") (name "unconnected-(U11-~{CLR}-Pad1)") (class "Default")
      (node (ref "U11") (pin "1") (pinfunction "~{CLR}_1") (pintype "input+no_connect"))
    )
  )
)
